# Order.net
KiCad netlist of a schematic drawn in EAGLE
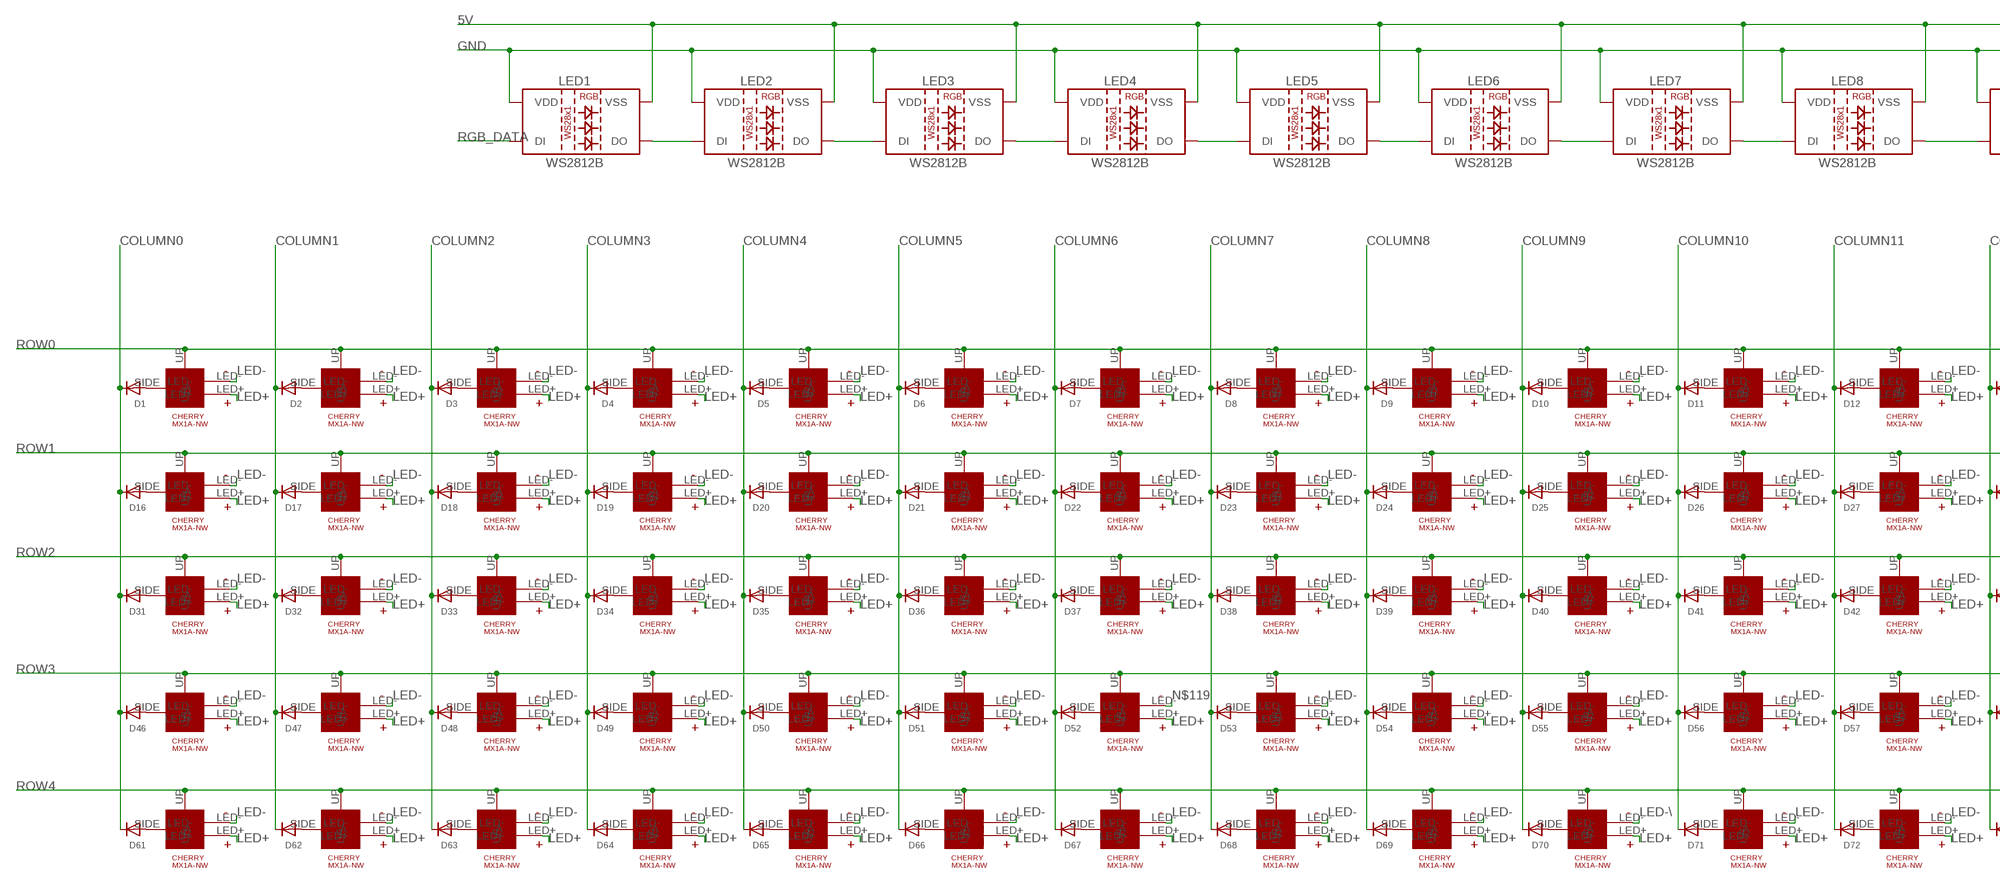
[diagram p0: schematic, sheet 1, part 1 of 2]
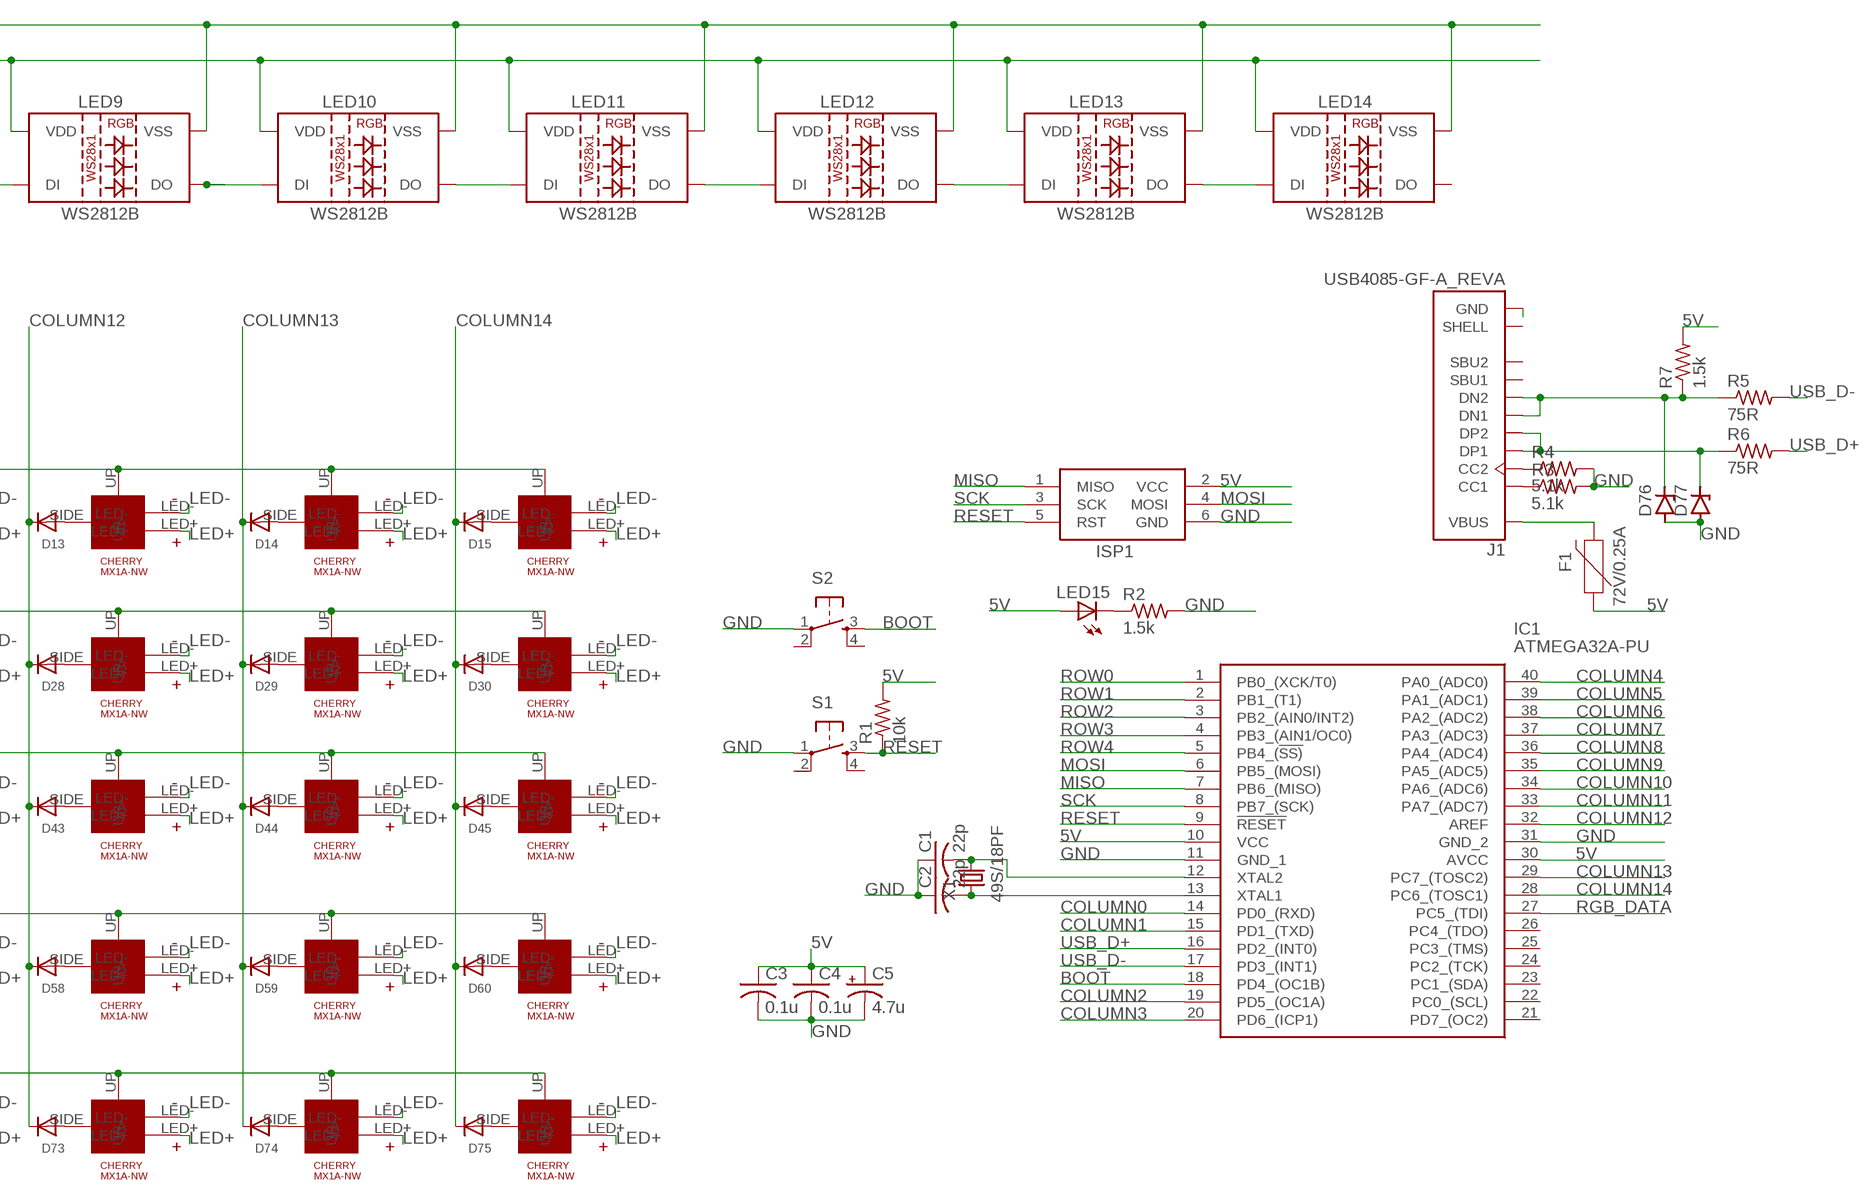
[diagram p1: schematic, sheet 1, part 2 of 2]

(export (version "E")
  (design (tool "Eeschema 10.0.6"))
  (components
    (comp (ref "C1")
      (value "22p")
      (footprint "eagle-import:C025-025X050")
      (libsource (lib "eagle-import") (part "C-US025-025X050"))
    )
    (comp (ref "C2")
      (value "22p")
      (footprint "eagle-import:C025-025X050")
      (libsource (lib "eagle-import") (part "C-US025-025X050"))
    )
    (comp (ref "C3")
      (value "0.1u")
      (footprint "eagle-import:C025-025X050")
      (libsource (lib "eagle-import") (part "C-US025-025X050"))
    )
    (comp (ref "C4")
      (value "0.1u")
      (footprint "eagle-import:C025-025X050")
      (libsource (lib "eagle-import") (part "C-US025-025X050"))
    )
    (comp (ref "C5")
      (value "4.7u")
      (footprint "eagle-import:E2-4")
      (libsource (lib "eagle-import") (part "CPOL-USE2-4"))
    )
    (comp (ref "D1")
      (value "DIODEDO-1N4148")
      (footprint "eagle-import:DO-1N4148")
      (libsource (lib "eagle-import") (part "DIODEDO-1N4148"))
    )
    (comp (ref "D2")
      (value "DIODEDO-1N4148")
      (footprint "eagle-import:DO-1N4148")
      (libsource (lib "eagle-import") (part "DIODEDO-1N4148"))
    )
    (comp (ref "D3")
      (value "DIODEDO-1N4148")
      (footprint "eagle-import:DO-1N4148")
      (libsource (lib "eagle-import") (part "DIODEDO-1N4148"))
    )
    (comp (ref "D4")
      (value "DIODEDO-1N4148")
      (footprint "eagle-import:DO-1N4148")
      (libsource (lib "eagle-import") (part "DIODEDO-1N4148"))
    )
    (comp (ref "D5")
      (value "DIODEDO-1N4148")
      (footprint "eagle-import:DO-1N4148")
      (libsource (lib "eagle-import") (part "DIODEDO-1N4148"))
    )
    (comp (ref "D6")
      (value "DIODEDO-1N4148")
      (footprint "eagle-import:DO-1N4148")
      (libsource (lib "eagle-import") (part "DIODEDO-1N4148"))
    )
    (comp (ref "D7")
      (value "DIODEDO-1N4148")
      (footprint "eagle-import:DO-1N4148")
      (libsource (lib "eagle-import") (part "DIODEDO-1N4148"))
    )
    (comp (ref "D8")
      (value "DIODEDO-1N4148")
      (footprint "eagle-import:DO-1N4148")
      (libsource (lib "eagle-import") (part "DIODEDO-1N4148"))
    )
    (comp (ref "D9")
      (value "DIODEDO-1N4148")
      (footprint "eagle-import:DO-1N4148")
      (libsource (lib "eagle-import") (part "DIODEDO-1N4148"))
    )
    (comp (ref "D10")
      (value "DIODEDO-1N4148")
      (footprint "eagle-import:DO-1N4148")
      (libsource (lib "eagle-import") (part "DIODEDO-1N4148"))
    )
    (comp (ref "D11")
      (value "DIODEDO-1N4148")
      (footprint "eagle-import:DO-1N4148")
      (libsource (lib "eagle-import") (part "DIODEDO-1N4148"))
    )
    (comp (ref "D12")
      (value "DIODEDO-1N4148")
      (footprint "eagle-import:DO-1N4148")
      (libsource (lib "eagle-import") (part "DIODEDO-1N4148"))
    )
    (comp (ref "D13")
      (value "DIODEDO-1N4148")
      (footprint "eagle-import:DO-1N4148")
      (libsource (lib "eagle-import") (part "DIODEDO-1N4148"))
    )
    (comp (ref "D14")
      (value "DIODEDO-1N4148")
      (footprint "eagle-import:DO-1N4148")
      (libsource (lib "eagle-import") (part "DIODEDO-1N4148"))
    )
    (comp (ref "D15")
      (value "DIODEDO-1N4148")
      (footprint "eagle-import:DO-1N4148")
      (libsource (lib "eagle-import") (part "DIODEDO-1N4148"))
    )
    (comp (ref "D16")
      (value "DIODEDO-1N4148")
      (footprint "eagle-import:DO-1N4148")
      (libsource (lib "eagle-import") (part "DIODEDO-1N4148"))
    )
    (comp (ref "D17")
      (value "DIODEDO-1N4148")
      (footprint "eagle-import:DO-1N4148")
      (libsource (lib "eagle-import") (part "DIODEDO-1N4148"))
    )
    (comp (ref "D18")
      (value "DIODEDO-1N4148")
      (footprint "eagle-import:DO-1N4148")
      (libsource (lib "eagle-import") (part "DIODEDO-1N4148"))
    )
    (comp (ref "D19")
      (value "DIODEDO-1N4148")
      (footprint "eagle-import:DO-1N4148")
      (libsource (lib "eagle-import") (part "DIODEDO-1N4148"))
    )
    (comp (ref "D20")
      (value "DIODEDO-1N4148")
      (footprint "eagle-import:DO-1N4148")
      (libsource (lib "eagle-import") (part "DIODEDO-1N4148"))
    )
    (comp (ref "D21")
      (value "DIODEDO-1N4148")
      (footprint "eagle-import:DO-1N4148")
      (libsource (lib "eagle-import") (part "DIODEDO-1N4148"))
    )
    (comp (ref "D22")
      (value "DIODEDO-1N4148")
      (footprint "eagle-import:DO-1N4148")
      (libsource (lib "eagle-import") (part "DIODEDO-1N4148"))
    )
    (comp (ref "D23")
      (value "DIODEDO-1N4148")
      (footprint "eagle-import:DO-1N4148")
      (libsource (lib "eagle-import") (part "DIODEDO-1N4148"))
    )
    (comp (ref "D24")
      (value "DIODEDO-1N4148")
      (footprint "eagle-import:DO-1N4148")
      (libsource (lib "eagle-import") (part "DIODEDO-1N4148"))
    )
    (comp (ref "D25")
      (value "DIODEDO-1N4148")
      (footprint "eagle-import:DO-1N4148")
      (libsource (lib "eagle-import") (part "DIODEDO-1N4148"))
    )
    (comp (ref "D26")
      (value "DIODEDO-1N4148")
      (footprint "eagle-import:DO-1N4148")
      (libsource (lib "eagle-import") (part "DIODEDO-1N4148"))
    )
    (comp (ref "D27")
      (value "DIODEDO-1N4148")
      (footprint "eagle-import:DO-1N4148")
      (libsource (lib "eagle-import") (part "DIODEDO-1N4148"))
    )
    (comp (ref "D28")
      (value "DIODEDO-1N4148")
      (footprint "eagle-import:DO-1N4148")
      (libsource (lib "eagle-import") (part "DIODEDO-1N4148"))
    )
    (comp (ref "D29")
      (value "DIODEDO-1N4148")
      (footprint "eagle-import:DO-1N4148")
      (libsource (lib "eagle-import") (part "DIODEDO-1N4148"))
    )
    (comp (ref "D30")
      (value "DIODEDO-1N4148")
      (footprint "eagle-import:DO-1N4148")
      (libsource (lib "eagle-import") (part "DIODEDO-1N4148"))
    )
    (comp (ref "D31")
      (value "DIODEDO-1N4148")
      (footprint "eagle-import:DO-1N4148")
      (libsource (lib "eagle-import") (part "DIODEDO-1N4148"))
    )
    (comp (ref "D32")
      (value "DIODEDO-1N4148")
      (footprint "eagle-import:DO-1N4148")
      (libsource (lib "eagle-import") (part "DIODEDO-1N4148"))
    )
    (comp (ref "D33")
      (value "DIODEDO-1N4148")
      (footprint "eagle-import:DO-1N4148")
      (libsource (lib "eagle-import") (part "DIODEDO-1N4148"))
    )
    (comp (ref "D34")
      (value "DIODEDO-1N4148")
      (footprint "eagle-import:DO-1N4148")
      (libsource (lib "eagle-import") (part "DIODEDO-1N4148"))
    )
    (comp (ref "D35")
      (value "DIODEDO-1N4148")
      (footprint "eagle-import:DO-1N4148")
      (libsource (lib "eagle-import") (part "DIODEDO-1N4148"))
    )
    (comp (ref "D36")
      (value "DIODEDO-1N4148")
      (footprint "eagle-import:DO-1N4148")
      (libsource (lib "eagle-import") (part "DIODEDO-1N4148"))
    )
    (comp (ref "D37")
      (value "DIODEDO-1N4148")
      (footprint "eagle-import:DO-1N4148")
      (libsource (lib "eagle-import") (part "DIODEDO-1N4148"))
    )
    (comp (ref "D38")
      (value "DIODEDO-1N4148")
      (footprint "eagle-import:DO-1N4148")
      (libsource (lib "eagle-import") (part "DIODEDO-1N4148"))
    )
    (comp (ref "D39")
      (value "DIODEDO-1N4148")
      (footprint "eagle-import:DO-1N4148")
      (libsource (lib "eagle-import") (part "DIODEDO-1N4148"))
    )
    (comp (ref "D40")
      (value "DIODEDO-1N4148")
      (footprint "eagle-import:DO-1N4148")
      (libsource (lib "eagle-import") (part "DIODEDO-1N4148"))
    )
    (comp (ref "D41")
      (value "DIODEDO-1N4148")
      (footprint "eagle-import:DO-1N4148")
      (libsource (lib "eagle-import") (part "DIODEDO-1N4148"))
    )
    (comp (ref "D42")
      (value "DIODEDO-1N4148")
      (footprint "eagle-import:DO-1N4148")
      (libsource (lib "eagle-import") (part "DIODEDO-1N4148"))
    )
    (comp (ref "D43")
      (value "DIODEDO-1N4148")
      (footprint "eagle-import:DO-1N4148")
      (libsource (lib "eagle-import") (part "DIODEDO-1N4148"))
    )
    (comp (ref "D44")
      (value "DIODEDO-1N4148")
      (footprint "eagle-import:DO-1N4148")
      (libsource (lib "eagle-import") (part "DIODEDO-1N4148"))
    )
    (comp (ref "D45")
      (value "DIODEDO-1N4148")
      (footprint "eagle-import:DO-1N4148")
      (libsource (lib "eagle-import") (part "DIODEDO-1N4148"))
    )
    (comp (ref "D46")
      (value "DIODEDO-1N4148")
      (footprint "eagle-import:DO-1N4148")
      (libsource (lib "eagle-import") (part "DIODEDO-1N4148"))
    )
    (comp (ref "D47")
      (value "DIODEDO-1N4148")
      (footprint "eagle-import:DO-1N4148")
      (libsource (lib "eagle-import") (part "DIODEDO-1N4148"))
    )
    (comp (ref "D48")
      (value "DIODEDO-1N4148")
      (footprint "eagle-import:DO-1N4148")
      (libsource (lib "eagle-import") (part "DIODEDO-1N4148"))
    )
    (comp (ref "D49")
      (value "DIODEDO-1N4148")
      (footprint "eagle-import:DO-1N4148")
      (libsource (lib "eagle-import") (part "DIODEDO-1N4148"))
    )
    (comp (ref "D50")
      (value "DIODEDO-1N4148")
      (footprint "eagle-import:DO-1N4148")
      (libsource (lib "eagle-import") (part "DIODEDO-1N4148"))
    )
    (comp (ref "D51")
      (value "DIODEDO-1N4148")
      (footprint "eagle-import:DO-1N4148")
      (libsource (lib "eagle-import") (part "DIODEDO-1N4148"))
    )
    (comp (ref "D52")
      (value "DIODEDO-1N4148")
      (footprint "eagle-import:DO-1N4148")
      (libsource (lib "eagle-import") (part "DIODEDO-1N4148"))
    )
    (comp (ref "D53")
      (value "DIODEDO-1N4148")
      (footprint "eagle-import:DO-1N4148")
      (libsource (lib "eagle-import") (part "DIODEDO-1N4148"))
    )
    (comp (ref "D54")
      (value "DIODEDO-1N4148")
      (footprint "eagle-import:DO-1N4148")
      (libsource (lib "eagle-import") (part "DIODEDO-1N4148"))
    )
    (comp (ref "D55")
      (value "DIODEDO-1N4148")
      (footprint "eagle-import:DO-1N4148")
      (libsource (lib "eagle-import") (part "DIODEDO-1N4148"))
    )
    (comp (ref "D56")
      (value "DIODEDO-1N4148")
      (footprint "eagle-import:DO-1N4148")
      (libsource (lib "eagle-import") (part "DIODEDO-1N4148"))
    )
    (comp (ref "D57")
      (value "DIODEDO-1N4148")
      (footprint "eagle-import:DO-1N4148")
      (libsource (lib "eagle-import") (part "DIODEDO-1N4148"))
    )
    (comp (ref "D58")
      (value "DIODEDO-1N4148")
      (footprint "eagle-import:DO-1N4148")
      (libsource (lib "eagle-import") (part "DIODEDO-1N4148"))
    )
    (comp (ref "D59")
      (value "DIODEDO-1N4148")
      (footprint "eagle-import:DO-1N4148")
      (libsource (lib "eagle-import") (part "DIODEDO-1N4148"))
    )
    (comp (ref "D60")
      (value "DIODEDO-1N4148")
      (footprint "eagle-import:DO-1N4148")
      (libsource (lib "eagle-import") (part "DIODEDO-1N4148"))
    )
    (comp (ref "D61")
      (value "DIODEDO-1N4148")
      (footprint "eagle-import:DO-1N4148")
      (libsource (lib "eagle-import") (part "DIODEDO-1N4148"))
    )
    (comp (ref "D62")
      (value "DIODEDO-1N4148")
      (footprint "eagle-import:DO-1N4148")
      (libsource (lib "eagle-import") (part "DIODEDO-1N4148"))
    )
    (comp (ref "D63")
      (value "DIODEDO-1N4148")
      (footprint "eagle-import:DO-1N4148")
      (libsource (lib "eagle-import") (part "DIODEDO-1N4148"))
    )
    (comp (ref "D64")
      (value "DIODEDO-1N4148")
      (footprint "eagle-import:DO-1N4148")
      (libsource (lib "eagle-import") (part "DIODEDO-1N4148"))
    )
    (comp (ref "D65")
      (value "DIODEDO-1N4148")
      (footprint "eagle-import:DO-1N4148")
      (libsource (lib "eagle-import") (part "DIODEDO-1N4148"))
    )
    (comp (ref "D66")
      (value "DIODEDO-1N4148")
      (footprint "eagle-import:DO-1N4148")
      (libsource (lib "eagle-import") (part "DIODEDO-1N4148"))
    )
    (comp (ref "D67")
      (value "DIODEDO-1N4148")
      (footprint "eagle-import:DO-1N4148")
      (libsource (lib "eagle-import") (part "DIODEDO-1N4148"))
    )
    (comp (ref "D68")
      (value "DIODEDO-1N4148")
      (footprint "eagle-import:DO-1N4148")
      (libsource (lib "eagle-import") (part "DIODEDO-1N4148"))
    )
    (comp (ref "D69")
      (value "DIODEDO-1N4148")
      (footprint "eagle-import:DO-1N4148")
      (libsource (lib "eagle-import") (part "DIODEDO-1N4148"))
    )
    (comp (ref "D70")
      (value "DIODEDO-1N4148")
      (footprint "eagle-import:DO-1N4148")
      (libsource (lib "eagle-import") (part "DIODEDO-1N4148"))
    )
    (comp (ref "D71")
      (value "DIODEDO-1N4148")
      (footprint "eagle-import:DO-1N4148")
      (libsource (lib "eagle-import") (part "DIODEDO-1N4148"))
    )
    (comp (ref "D72")
      (value "DIODEDO-1N4148")
      (footprint "eagle-import:DO-1N4148")
      (libsource (lib "eagle-import") (part "DIODEDO-1N4148"))
    )
    (comp (ref "D73")
      (value "DIODEDO-1N4148")
      (footprint "eagle-import:DO-1N4148")
      (libsource (lib "eagle-import") (part "DIODEDO-1N4148"))
    )
    (comp (ref "D74")
      (value "DIODEDO-1N4148")
      (footprint "eagle-import:DO-1N4148")
      (libsource (lib "eagle-import") (part "DIODEDO-1N4148"))
    )
    (comp (ref "D75")
      (value "DIODEDO-1N4148")
      (footprint "eagle-import:DO-1N4148")
      (libsource (lib "eagle-import") (part "DIODEDO-1N4148"))
    )
    (comp (ref "D76")
      (value "ZENER-DIODEDO34-7")
      (footprint "eagle-import:DO34Z7")
      (libsource (lib "eagle-import") (part "ZENER-DIODEDO34-7"))
    )
    (comp (ref "D77")
      (value "ZENER-DIODEDO34-7")
      (footprint "eagle-import:DO34Z7")
      (libsource (lib "eagle-import") (part "ZENER-DIODEDO34-7"))
    )
    (comp (ref "F1")
      (value "72V/0.25A")
      (footprint "eagle-import:PTH")
      (libsource (lib "eagle-import") (part "PPTC_PTH"))
    )
    (comp (ref "IC1")
      (value "ATMEGA32A-PU")
      (footprint "eagle-import:DIP1556W56P254L5232H483Q40N")
      (fields (field (name "MOUSER_PART_NUMBER") "556-ATMEGA32A-PU"))
      (libsource (lib "eagle-import") (part "ATMEGA32A-PU"))
    )
    (comp (ref "ISP1")
      (value "AVRISP-6")
      (footprint "eagle-import:AVRISP")
      (libsource (lib "eagle-import") (part "AVRISP-6"))
    )
    (comp (ref "J1")
      (value "USB4085-GF-A_REVA")
      (footprint "eagle-import:GCT_USB4085-GF-A_REVA")
      (fields
        (field (name "DIGI-KEY_PART_NUMBER") "2073-USB4085-GF-ACT-ND")
        (field (name "MF") "Global Connector Technology")
        (field (name "MP") "USB4085-GF-A")
      )
      (libsource (lib "eagle-import") (part "USB4085-GF-A_REVA"))
    )
    (comp (ref "LED1")
      (value "WS2812B")
      (footprint "eagle-import:WS2812B")
      (libsource (lib "eagle-import") (part "WS2812B"))
    )
    (comp (ref "LED2")
      (value "WS2812B")
      (footprint "eagle-import:WS2812B")
      (libsource (lib "eagle-import") (part "WS2812B"))
    )
    (comp (ref "LED3")
      (value "WS2812B")
      (footprint "eagle-import:WS2812B")
      (libsource (lib "eagle-import") (part "WS2812B"))
    )
    (comp (ref "LED4")
      (value "WS2812B")
      (footprint "eagle-import:WS2812B")
      (libsource (lib "eagle-import") (part "WS2812B"))
    )
    (comp (ref "LED5")
      (value "WS2812B")
      (footprint "eagle-import:WS2812B")
      (libsource (lib "eagle-import") (part "WS2812B"))
    )
    (comp (ref "LED6")
      (value "WS2812B")
      (footprint "eagle-import:WS2812B")
      (libsource (lib "eagle-import") (part "WS2812B"))
    )
    (comp (ref "LED7")
      (value "WS2812B")
      (footprint "eagle-import:WS2812B")
      (libsource (lib "eagle-import") (part "WS2812B"))
    )
    (comp (ref "LED8")
      (value "WS2812B")
      (footprint "eagle-import:WS2812B")
      (libsource (lib "eagle-import") (part "WS2812B"))
    )
    (comp (ref "LED9")
      (value "WS2812B")
      (footprint "eagle-import:WS2812B")
      (libsource (lib "eagle-import") (part "WS2812B"))
    )
    (comp (ref "LED10")
      (value "WS2812B")
      (footprint "eagle-import:WS2812B")
      (libsource (lib "eagle-import") (part "WS2812B"))
    )
    (comp (ref "LED11")
      (value "WS2812B")
      (footprint "eagle-import:WS2812B")
      (libsource (lib "eagle-import") (part "WS2812B"))
    )
    (comp (ref "LED12")
      (value "WS2812B")
      (footprint "eagle-import:WS2812B")
      (libsource (lib "eagle-import") (part "WS2812B"))
    )
    (comp (ref "LED13")
      (value "WS2812B")
      (footprint "eagle-import:WS2812B")
      (libsource (lib "eagle-import") (part "WS2812B"))
    )
    (comp (ref "LED14")
      (value "WS2812B")
      (footprint "eagle-import:WS2812B")
      (libsource (lib "eagle-import") (part "WS2812B"))
    )
    (comp (ref "LED15")
      (value "LED3MM")
      (footprint "eagle-import:LED3MM")
      (libsource (lib "eagle-import") (part "LED3MM"))
    )
    (comp (ref "R1")
      (value "10k")
      (footprint "eagle-import:0207_9")
      (libsource (lib "eagle-import") (part "R-US_0207/9"))
    )
    (comp (ref "R2")
      (value "1.5k")
      (footprint "eagle-import:0207_9")
      (libsource (lib "eagle-import") (part "R-US_0207/9"))
    )
    (comp (ref "R3")
      (value "5.1k")
      (footprint "eagle-import:0207_9")
      (libsource (lib "eagle-import") (part "R-US_0207/9"))
    )
    (comp (ref "R4")
      (value "5.1k")
      (footprint "eagle-import:0207_9")
      (libsource (lib "eagle-import") (part "R-US_0207/9"))
    )
    (comp (ref "R5")
      (value "75R")
      (footprint "eagle-import:0207_9")
      (libsource (lib "eagle-import") (part "R-US_0207/9"))
    )
    (comp (ref "R6")
      (value "75R")
      (footprint "eagle-import:0207_9")
      (libsource (lib "eagle-import") (part "R-US_0207/9"))
    )
    (comp (ref "R7")
      (value "1.5k")
      (footprint "eagle-import:0207_9")
      (libsource (lib "eagle-import") (part "R-US_0207/9"))
    )
    (comp (ref "S1")
      (value "TAC_SWITCHPTH")
      (footprint "eagle-import:TACTILE-PTH")
      (libsource (lib "eagle-import") (part "TAC_SWITCHPTH"))
    )
    (comp (ref "S2")
      (value "TAC_SWITCHPTH")
      (footprint "eagle-import:TACTILE-PTH")
      (libsource (lib "eagle-import") (part "TAC_SWITCHPTH"))
    )
    (comp (ref "U$1")
      (value "CHERRY-MX1A-E1NW-LED")
      (footprint "eagle-import:CHERRYMX-NN-LED")
      (libsource (lib "eagle-import") (part "CHERRY-MX1A-E1NW-LED"))
    )
    (comp (ref "U$2")
      (value "CHERRY-MX1A-E1NW-LED")
      (footprint "eagle-import:CHERRYMX-NN-LED")
      (libsource (lib "eagle-import") (part "CHERRY-MX1A-E1NW-LED"))
    )
    (comp (ref "U$3")
      (value "CHERRY-MX1A-E1NW-LED")
      (footprint "eagle-import:CHERRYMX-NN-LED")
      (libsource (lib "eagle-import") (part "CHERRY-MX1A-E1NW-LED"))
    )
    (comp (ref "U$4")
      (value "CHERRY-MX1A-E1NW-LED")
      (footprint "eagle-import:CHERRYMX-NN-LED")
      (libsource (lib "eagle-import") (part "CHERRY-MX1A-E1NW-LED"))
    )
    (comp (ref "U$5")
      (value "CHERRY-MX1A-E1NW-LED")
      (footprint "eagle-import:CHERRYMX-NN-LED")
      (libsource (lib "eagle-import") (part "CHERRY-MX1A-E1NW-LED"))
    )
    (comp (ref "U$6")
      (value "CHERRY-MX1A-E1NW-LED")
      (footprint "eagle-import:CHERRYMX-NN-LED")
      (libsource (lib "eagle-import") (part "CHERRY-MX1A-E1NW-LED"))
    )
    (comp (ref "U$7")
      (value "CHERRY-MX1A-E1NW-LED")
      (footprint "eagle-import:CHERRYMX-NN-LED")
      (libsource (lib "eagle-import") (part "CHERRY-MX1A-E1NW-LED"))
    )
    (comp (ref "U$8")
      (value "CHERRY-MX1A-E1NW-LED")
      (footprint "eagle-import:CHERRYMX-NN-LED")
      (libsource (lib "eagle-import") (part "CHERRY-MX1A-E1NW-LED"))
    )
    (comp (ref "U$9")
      (value "CHERRY-MX1A-E1NW-LED")
      (footprint "eagle-import:CHERRYMX-NN-LED")
      (libsource (lib "eagle-import") (part "CHERRY-MX1A-E1NW-LED"))
    )
    (comp (ref "U$10")
      (value "CHERRY-MX1A-E1NW-LED")
      (footprint "eagle-import:CHERRYMX-NN-LED")
      (libsource (lib "eagle-import") (part "CHERRY-MX1A-E1NW-LED"))
    )
    (comp (ref "U$11")
      (value "CHERRY-MX1A-E1NW-LED")
      (footprint "eagle-import:CHERRYMX-NN-LED")
      (libsource (lib "eagle-import") (part "CHERRY-MX1A-E1NW-LED"))
    )
    (comp (ref "U$12")
      (value "CHERRY-MX1A-E1NW-LED")
      (footprint "eagle-import:CHERRYMX-NN-LED")
      (libsource (lib "eagle-import") (part "CHERRY-MX1A-E1NW-LED"))
    )
    (comp (ref "U$13")
      (value "CHERRY-MX1A-E1NW-LED")
      (footprint "eagle-import:CHERRYMX-NN-LED")
      (libsource (lib "eagle-import") (part "CHERRY-MX1A-E1NW-LED"))
    )
    (comp (ref "U$14")
      (value "CHERRY-MX1A-E1NW-LED")
      (footprint "eagle-import:CHERRYMX-NN-LED")
      (libsource (lib "eagle-import") (part "CHERRY-MX1A-E1NW-LED"))
    )
    (comp (ref "U$15")
      (value "CHERRY-MX1A-E1NW-LED")
      (footprint "eagle-import:CHERRYMX-NN-LED")
      (libsource (lib "eagle-import") (part "CHERRY-MX1A-E1NW-LED"))
    )
    (comp (ref "U$16")
      (value "CHERRY-MX1A-E1NW-LED")
      (footprint "eagle-import:CHERRYMX-NN-LED")
      (libsource (lib "eagle-import") (part "CHERRY-MX1A-E1NW-LED"))
    )
    (comp (ref "U$17")
      (value "CHERRY-MX1A-E1NW-LED")
      (footprint "eagle-import:CHERRYMX-NN-LED")
      (libsource (lib "eagle-import") (part "CHERRY-MX1A-E1NW-LED"))
    )
    (comp (ref "U$18")
      (value "CHERRY-MX1A-E1NW-LED")
      (footprint "eagle-import:CHERRYMX-NN-LED")
      (libsource (lib "eagle-import") (part "CHERRY-MX1A-E1NW-LED"))
    )
    (comp (ref "U$19")
      (value "CHERRY-MX1A-E1NW-LED")
      (footprint "eagle-import:CHERRYMX-NN-LED")
      (libsource (lib "eagle-import") (part "CHERRY-MX1A-E1NW-LED"))
    )
    (comp (ref "U$20")
      (value "CHERRY-MX1A-E1NW-LED")
      (footprint "eagle-import:CHERRYMX-NN-LED")
      (libsource (lib "eagle-import") (part "CHERRY-MX1A-E1NW-LED"))
    )
    (comp (ref "U$21")
      (value "CHERRY-MX1A-E1NW-LED")
      (footprint "eagle-import:CHERRYMX-NN-LED")
      (libsource (lib "eagle-import") (part "CHERRY-MX1A-E1NW-LED"))
    )
    (comp (ref "U$22")
      (value "CHERRY-MX1A-E1NW-LED")
      (footprint "eagle-import:CHERRYMX-NN-LED")
      (libsource (lib "eagle-import") (part "CHERRY-MX1A-E1NW-LED"))
    )
    (comp (ref "U$23")
      (value "CHERRY-MX1A-E1NW-LED")
      (footprint "eagle-import:CHERRYMX-NN-LED")
      (libsource (lib "eagle-import") (part "CHERRY-MX1A-E1NW-LED"))
    )
    (comp (ref "U$24")
      (value "CHERRY-MX1A-E1NW-LED")
      (footprint "eagle-import:CHERRYMX-NN-LED")
      (libsource (lib "eagle-import") (part "CHERRY-MX1A-E1NW-LED"))
    )
    (comp (ref "U$25")
      (value "CHERRY-MX1A-E1NW-LED")
      (footprint "eagle-import:CHERRYMX-NN-LED")
      (libsource (lib "eagle-import") (part "CHERRY-MX1A-E1NW-LED"))
    )
    (comp (ref "U$26")
      (value "CHERRY-MX1A-E1NW-LED")
      (footprint "eagle-import:CHERRYMX-NN-LED")
      (libsource (lib "eagle-import") (part "CHERRY-MX1A-E1NW-LED"))
    )
    (comp (ref "U$27")
      (value "CHERRY-MX1A-E1NW-LED")
      (footprint "eagle-import:CHERRYMX-NN-LED")
      (libsource (lib "eagle-import") (part "CHERRY-MX1A-E1NW-LED"))
    )
    (comp (ref "U$28")
      (value "CHERRY-MX1A-E1NW-LED")
      (footprint "eagle-import:CHERRYMX-NN-LED")
      (libsource (lib "eagle-import") (part "CHERRY-MX1A-E1NW-LED"))
    )
    (comp (ref "U$29")
      (value "CHERRY-MX1A-E1NW-LED")
      (footprint "eagle-import:CHERRYMX-NN-LED")
      (libsource (lib "eagle-import") (part "CHERRY-MX1A-E1NW-LED"))
    )
    (comp (ref "U$30")
      (value "CHERRY-MX1A-E1NW-LED")
      (footprint "eagle-import:CHERRYMX-NN-LED")
      (libsource (lib "eagle-import") (part "CHERRY-MX1A-E1NW-LED"))
    )
    (comp (ref "U$31")
      (value "CHERRY-MX1A-E1NW-LED")
      (footprint "eagle-import:CHERRYMX-NN-LED")
      (libsource (lib "eagle-import") (part "CHERRY-MX1A-E1NW-LED"))
    )
    (comp (ref "U$32")
      (value "CHERRY-MX1A-E1NW-LED")
      (footprint "eagle-import:CHERRYMX-NN-LED")
      (libsource (lib "eagle-import") (part "CHERRY-MX1A-E1NW-LED"))
    )
    (comp (ref "U$33")
      (value "CHERRY-MX1A-E1NW-LED")
      (footprint "eagle-import:CHERRYMX-NN-LED")
      (libsource (lib "eagle-import") (part "CHERRY-MX1A-E1NW-LED"))
    )
    (comp (ref "U$34")
      (value "CHERRY-MX1A-E1NW-LED")
      (footprint "eagle-import:CHERRYMX-NN-LED")
      (libsource (lib "eagle-import") (part "CHERRY-MX1A-E1NW-LED"))
    )
    (comp (ref "U$35")
      (value "CHERRY-MX1A-E1NW-LED")
      (footprint "eagle-import:CHERRYMX-NN-LED")
      (libsource (lib "eagle-import") (part "CHERRY-MX1A-E1NW-LED"))
    )
    (comp (ref "U$36")
      (value "CHERRY-MX1A-E1NW-LED")
      (footprint "eagle-import:CHERRYMX-NN-LED")
      (libsource (lib "eagle-import") (part "CHERRY-MX1A-E1NW-LED"))
    )
    (comp (ref "U$37")
      (value "CHERRY-MX1A-E1NW-LED")
      (footprint "eagle-import:CHERRYMX-NN-LED")
      (libsource (lib "eagle-import") (part "CHERRY-MX1A-E1NW-LED"))
    )
    (comp (ref "U$38")
      (value "CHERRY-MX1A-E1NW-LED")
      (footprint "eagle-import:CHERRYMX-NN-LED")
      (libsource (lib "eagle-import") (part "CHERRY-MX1A-E1NW-LED"))
    )
    (comp (ref "U$39")
      (value "CHERRY-MX1A-E1NW-LED")
      (footprint "eagle-import:CHERRYMX-NN-LED")
      (libsource (lib "eagle-import") (part "CHERRY-MX1A-E1NW-LED"))
    )
    (comp (ref "U$40")
      (value "CHERRY-MX1A-E1NW-LED")
      (footprint "eagle-import:CHERRYMX-NN-LED")
      (libsource (lib "eagle-import") (part "CHERRY-MX1A-E1NW-LED"))
    )
    (comp (ref "U$41")
      (value "CHERRY-MX1A-E1NW-LED")
      (footprint "eagle-import:CHERRYMX-NN-LED")
      (libsource (lib "eagle-import") (part "CHERRY-MX1A-E1NW-LED"))
    )
    (comp (ref "U$42")
      (value "CHERRY-MX1A-E1NW-LED")
      (footprint "eagle-import:CHERRYMX-NN-LED")
      (libsource (lib "eagle-import") (part "CHERRY-MX1A-E1NW-LED"))
    )
    (comp (ref "U$43")
      (value "CHERRY-MX1A-E1NW-LED")
      (footprint "eagle-import:CHERRYMX-NN-LED")
      (libsource (lib "eagle-import") (part "CHERRY-MX1A-E1NW-LED"))
    )
    (comp (ref "U$44")
      (value "CHERRY-MX1A-E1NW-LED")
      (footprint "eagle-import:CHERRYMX-NN-LED")
      (libsource (lib "eagle-import") (part "CHERRY-MX1A-E1NW-LED"))
    )
    (comp (ref "U$45")
      (value "CHERRY-MX1A-E1NW-LED")
      (footprint "eagle-import:CHERRYMX-NN-LED")
      (libsource (lib "eagle-import") (part "CHERRY-MX1A-E1NW-LED"))
    )
    (comp (ref "U$46")
      (value "CHERRY-MX1A-E1NW-LED")
      (footprint "eagle-import:CHERRYMX-NN-LED")
      (libsource (lib "eagle-import") (part "CHERRY-MX1A-E1NW-LED"))
    )
    (comp (ref "U$47")
      (value "CHERRY-MX1A-E1NW-LED")
      (footprint "eagle-import:CHERRYMX-NN-LED")
      (libsource (lib "eagle-import") (part "CHERRY-MX1A-E1NW-LED"))
    )
    (comp (ref "U$48")
      (value "CHERRY-MX1A-E1NW-LED")
      (footprint "eagle-import:CHERRYMX-NN-LED")
      (libsource (lib "eagle-import") (part "CHERRY-MX1A-E1NW-LED"))
    )
    (comp (ref "U$49")
      (value "CHERRY-MX1A-E1NW-LED")
      (footprint "eagle-import:CHERRYMX-NN-LED")
      (libsource (lib "eagle-import") (part "CHERRY-MX1A-E1NW-LED"))
    )
    (comp (ref "U$50")
      (value "CHERRY-MX1A-E1NW-LED")
      (footprint "eagle-import:CHERRYMX-NN-LED")
      (libsource (lib "eagle-import") (part "CHERRY-MX1A-E1NW-LED"))
    )
    (comp (ref "U$51")
      (value "CHERRY-MX1A-E1NW-LED")
      (footprint "eagle-import:CHERRYMX-NN-LED")
      (libsource (lib "eagle-import") (part "CHERRY-MX1A-E1NW-LED"))
    )
    (comp (ref "U$52")
      (value "CHERRY-MX1A-E1NW-LED")
      (footprint "eagle-import:CHERRYMX-NN-LED")
      (libsource (lib "eagle-import") (part "CHERRY-MX1A-E1NW-LED"))
    )
    (comp (ref "U$53")
      (value "CHERRY-MX1A-E1NW-LED")
      (footprint "eagle-import:CHERRYMX-NN-LED")
      (libsource (lib "eagle-import") (part "CHERRY-MX1A-E1NW-LED"))
    )
    (comp (ref "U$54")
      (value "CHERRY-MX1A-E1NW-LED")
      (footprint "eagle-import:CHERRYMX-NN-LED")
      (libsource (lib "eagle-import") (part "CHERRY-MX1A-E1NW-LED"))
    )
    (comp (ref "U$55")
      (value "CHERRY-MX1A-E1NW-LED")
      (footprint "eagle-import:CHERRYMX-NN-LED")
      (libsource (lib "eagle-import") (part "CHERRY-MX1A-E1NW-LED"))
    )
    (comp (ref "U$56")
      (value "CHERRY-MX1A-E1NW-LED")
      (footprint "eagle-import:CHERRYMX-NN-LED")
      (libsource (lib "eagle-import") (part "CHERRY-MX1A-E1NW-LED"))
    )
    (comp (ref "U$57")
      (value "CHERRY-MX1A-E1NW-LED")
      (footprint "eagle-import:CHERRYMX-NN-LED")
      (libsource (lib "eagle-import") (part "CHERRY-MX1A-E1NW-LED"))
    )
    (comp (ref "U$58")
      (value "CHERRY-MX1A-E1NW-LED")
      (footprint "eagle-import:CHERRYMX-NN-LED")
      (libsource (lib "eagle-import") (part "CHERRY-MX1A-E1NW-LED"))
    )
    (comp (ref "U$59")
      (value "CHERRY-MX1A-E1NW-LED")
      (footprint "eagle-import:CHERRYMX-NN-LED")
      (libsource (lib "eagle-import") (part "CHERRY-MX1A-E1NW-LED"))
    )
    (comp (ref "U$60")
      (value "CHERRY-MX1A-E1NW-LED")
      (footprint "eagle-import:CHERRYMX-NN-LED")
      (libsource (lib "eagle-import") (part "CHERRY-MX1A-E1NW-LED"))
    )
    (comp (ref "U$61")
      (value "CHERRY-MX1A-E1NW-LED")
      (footprint "eagle-import:CHERRYMX-NN-LED")
      (libsource (lib "eagle-import") (part "CHERRY-MX1A-E1NW-LED"))
    )
    (comp (ref "U$62")
      (value "CHERRY-MX1A-E1NW-LED")
      (footprint "eagle-import:CHERRYMX-NN-LED")
      (libsource (lib "eagle-import") (part "CHERRY-MX1A-E1NW-LED"))
    )
    (comp (ref "U$63")
      (value "CHERRY-MX1A-E1NW-LED")
      (footprint "eagle-import:CHERRYMX-NN-LED")
      (libsource (lib "eagle-import") (part "CHERRY-MX1A-E1NW-LED"))
    )
    (comp (ref "U$64")
      (value "CHERRY-MX1A-E1NW-LED")
      (footprint "eagle-import:CHERRYMX-NN-LED")
      (libsource (lib "eagle-import") (part "CHERRY-MX1A-E1NW-LED"))
    )
    (comp (ref "U$65")
      (value "CHERRY-MX1A-E1NW-LED")
      (footprint "eagle-import:CHERRYMX-NN-LED")
      (libsource (lib "eagle-import") (part "CHERRY-MX1A-E1NW-LED"))
    )
    (comp (ref "U$66")
      (value "CHERRY-MX1A-E1NW-LED")
      (footprint "eagle-import:CHERRYMX-NN-LED")
      (libsource (lib "eagle-import") (part "CHERRY-MX1A-E1NW-LED"))
    )
    (comp (ref "U$67")
      (value "CHERRY-MX1A-E1NW-LED")
      (footprint "eagle-import:CHERRYMX-NN-LED")
      (libsource (lib "eagle-import") (part "CHERRY-MX1A-E1NW-LED"))
    )
    (comp (ref "U$68")
      (value "CHERRY-MX1A-E1NW-LED")
      (footprint "eagle-import:CHERRYMX-NN-LED")
      (libsource (lib "eagle-import") (part "CHERRY-MX1A-E1NW-LED"))
    )
    (comp (ref "U$69")
      (value "CHERRY-MX1A-E1NW-LED")
      (footprint "eagle-import:CHERRYMX-NN-LED")
      (libsource (lib "eagle-import") (part "CHERRY-MX1A-E1NW-LED"))
    )
    (comp (ref "U$70")
      (value "CHERRY-MX1A-E1NW-LED")
      (footprint "eagle-import:CHERRYMX-NN-LED")
      (libsource (lib "eagle-import") (part "CHERRY-MX1A-E1NW-LED"))
    )
    (comp (ref "U$71")
      (value "CHERRY-MX1A-E1NW-LED")
      (footprint "eagle-import:CHERRYMX-NN-LED")
      (libsource (lib "eagle-import") (part "CHERRY-MX1A-E1NW-LED"))
    )
    (comp (ref "U$72")
      (value "CHERRY-MX1A-E1NW-LED")
      (footprint "eagle-import:CHERRYMX-NN-LED")
      (libsource (lib "eagle-import") (part "CHERRY-MX1A-E1NW-LED"))
    )
    (comp (ref "U$73")
      (value "CHERRY-MX1A-E1NW-LED")
      (footprint "eagle-import:CHERRYMX-NN-LED")
      (libsource (lib "eagle-import") (part "CHERRY-MX1A-E1NW-LED"))
    )
    (comp (ref "U$74")
      (value "CHERRY-MX1A-E1NW-LED")
      (footprint "eagle-import:CHERRYMX-NN-LED")
      (libsource (lib "eagle-import") (part "CHERRY-MX1A-E1NW-LED"))
    )
    (comp (ref "U$75")
      (value "CHERRY-MX1A-E1NW-LED")
      (footprint "eagle-import:CHERRYMX-NN-LED")
      (libsource (lib "eagle-import") (part "CHERRY-MX1A-E1NW-LED"))
    )
    (comp (ref "X1")
      (value "49S/18PF")
      (footprint "eagle-import:XTAL_HC49")
      (fields (field (name "MANUFACTURER") "Xinhunjing ") (field (name "CREATED_BY") "PCBLayout.com"))
      (libsource (lib "eagle-import") (part "49S/18PF"))
    )
  )
  (nets
    (net (code "1") (name "/5V") (class "Default")
      (node (ref "C3") (pin "1") (pinfunction "1_1") (pintype "passive"))
      (node (ref "C4") (pin "1") (pinfunction "1_1") (pintype "passive"))
      (node (ref "C5") (pin "+") (pinfunction "+_+") (pintype "passive"))
      (node (ref "F1") (pin "P$1") (pinfunction "1_P$1") (pintype "bidirectional"))
      (node (ref "IC1") (pin "10") (pinfunction "VCC_10") (pintype "bidirectional"))
      (node (ref "IC1") (pin "30") (pinfunction "AVCC_30") (pintype "bidirectional"))
      (node (ref "ISP1") (pin "2") (pinfunction "VCC_2") (pintype "power_in"))
      (node (ref "LED1") (pin "3") (pinfunction "VSS_3") (pintype "bidirectional"))
      (node (ref "LED10") (pin "3") (pinfunction "VSS_3") (pintype "bidirectional"))
      (node (ref "LED11") (pin "3") (pinfunction "VSS_3") (pintype "bidirectional"))
      (node (ref "LED12") (pin "3") (pinfunction "VSS_3") (pintype "bidirectional"))
      (node (ref "LED13") (pin "3") (pinfunction "VSS_3") (pintype "bidirectional"))
      (node (ref "LED14") (pin "3") (pinfunction "VSS_3") (pintype "bidirectional"))
      (node (ref "LED15") (pin "A") (pinfunction "A_A") (pintype "passive"))
      (node (ref "LED2") (pin "3") (pinfunction "VSS_3") (pintype "bidirectional"))
      (node (ref "LED3") (pin "3") (pinfunction "VSS_3") (pintype "bidirectional"))
      (node (ref "LED4") (pin "3") (pinfunction "VSS_3") (pintype "bidirectional"))
      (node (ref "LED5") (pin "3") (pinfunction "VSS_3") (pintype "bidirectional"))
      (node (ref "LED6") (pin "3") (pinfunction "VSS_3") (pintype "bidirectional"))
      (node (ref "LED7") (pin "3") (pinfunction "VSS_3") (pintype "bidirectional"))
      (node (ref "LED8") (pin "3") (pinfunction "VSS_3") (pintype "bidirectional"))
      (node (ref "LED9") (pin "3") (pinfunction "VSS_3") (pintype "bidirectional"))
      (node (ref "R1") (pin "2") (pinfunction "2_2") (pintype "passive"))
      (node (ref "R7") (pin "2") (pinfunction "2_2") (pintype "passive"))
    )
    (net (code "2") (name "/BOOT") (class "Default")
      (node (ref "IC1") (pin "18") (pinfunction "PD4_(OC1B)_18") (pintype "bidirectional"))
      (node (ref "S2") (pin "3") (pinfunction "3_3") (pintype "passive"))
    )
    (net (code "3") (name "/COLUMN0") (class "Default")
      (node (ref "D1") (pin "C") (pinfunction "C_C") (pintype "passive"))
      (node (ref "D16") (pin "C") (pinfunction "C_C") (pintype "passive"))
      (node (ref "D31") (pin "C") (pinfunction "C_C") (pintype "passive"))
      (node (ref "D46") (pin "C") (pinfunction "C_C") (pintype "passive"))
      (node (ref "D61") (pin "C") (pinfunction "C_C") (pintype "passive"))
      (node (ref "IC1") (pin "14") (pinfunction "PD0_(RXD)_14") (pintype "bidirectional"))
    )
    (net (code "4") (name "/COLUMN1") (class "Default")
      (node (ref "D17") (pin "C") (pinfunction "C_C") (pintype "passive"))
      (node (ref "D2") (pin "C") (pinfunction "C_C") (pintype "passive"))
      (node (ref "D32") (pin "C") (pinfunction "C_C") (pintype "passive"))
      (node (ref "D47") (pin "C") (pinfunction "C_C") (pintype "passive"))
      (node (ref "D62") (pin "C") (pinfunction "C_C") (pintype "passive"))
      (node (ref "IC1") (pin "15") (pinfunction "PD1_(TXD)_15") (pintype "bidirectional"))
    )
    (net (code "5") (name "/COLUMN2") (class "Default")
      (node (ref "D18") (pin "C") (pinfunction "C_C") (pintype "passive"))
      (node (ref "D3") (pin "C") (pinfunction "C_C") (pintype "passive"))
      (node (ref "D33") (pin "C") (pinfunction "C_C") (pintype "passive"))
      (node (ref "D48") (pin "C") (pinfunction "C_C") (pintype "passive"))
      (node (ref "D63") (pin "C") (pinfunction "C_C") (pintype "passive"))
      (node (ref "IC1") (pin "19") (pinfunction "PD5_(OC1A)_19") (pintype "bidirectional"))
    )
    (net (code "6") (name "/COLUMN3") (class "Default")
      (node (ref "D19") (pin "C") (pinfunction "C_C") (pintype "passive"))
      (node (ref "D34") (pin "C") (pinfunction "C_C") (pintype "passive"))
      (node (ref "D4") (pin "C") (pinfunction "C_C") (pintype "passive"))
      (node (ref "D49") (pin "C") (pinfunction "C_C") (pintype "passive"))
      (node (ref "D64") (pin "C") (pinfunction "C_C") (pintype "passive"))
      (node (ref "IC1") (pin "20") (pinfunction "PD6_(ICP1)_20") (pintype "bidirectional"))
    )
    (net (code "7") (name "/COLUMN4") (class "Default")
      (node (ref "D20") (pin "C") (pinfunction "C_C") (pintype "passive"))
      (node (ref "D35") (pin "C") (pinfunction "C_C") (pintype "passive"))
      (node (ref "D5") (pin "C") (pinfunction "C_C") (pintype "passive"))
      (node (ref "D50") (pin "C") (pinfunction "C_C") (pintype "passive"))
      (node (ref "D65") (pin "C") (pinfunction "C_C") (pintype "passive"))
      (node (ref "IC1") (pin "40") (pinfunction "PA0_(ADC0)_40") (pintype "bidirectional"))
    )
    (net (code "8") (name "/COLUMN5") (class "Default")
      (node (ref "D21") (pin "C") (pinfunction "C_C") (pintype "passive"))
      (node (ref "D36") (pin "C") (pinfunction "C_C") (pintype "passive"))
      (node (ref "D51") (pin "C") (pinfunction "C_C") (pintype "passive"))
      (node (ref "D6") (pin "C") (pinfunction "C_C") (pintype "passive"))
      (node (ref "D66") (pin "C") (pinfunction "C_C") (pintype "passive"))
      (node (ref "IC1") (pin "39") (pinfunction "PA1_(ADC1)_39") (pintype "bidirectional"))
    )
    (net (code "9") (name "/COLUMN6") (class "Default")
      (node (ref "D22") (pin "C") (pinfunction "C_C") (pintype "passive"))
      (node (ref "D37") (pin "C") (pinfunction "C_C") (pintype "passive"))
      (node (ref "D52") (pin "C") (pinfunction "C_C") (pintype "passive"))
      (node (ref "D67") (pin "C") (pinfunction "C_C") (pintype "passive"))
      (node (ref "D7") (pin "C") (pinfunction "C_C") (pintype "passive"))
      (node (ref "IC1") (pin "38") (pinfunction "PA2_(ADC2)_38") (pintype "bidirectional"))
    )
    (net (code "10") (name "/COLUMN7") (class "Default")
      (node (ref "D23") (pin "C") (pinfunction "C_C") (pintype "passive"))
      (node (ref "D38") (pin "C") (pinfunction "C_C") (pintype "passive"))
      (node (ref "D53") (pin "C") (pinfunction "C_C") (pintype "passive"))
      (node (ref "D68") (pin "C") (pinfunction "C_C") (pintype "passive"))
      (node (ref "D8") (pin "C") (pinfunction "C_C") (pintype "passive"))
      (node (ref "IC1") (pin "37") (pinfunction "PA3_(ADC3)_37") (pintype "bidirectional"))
    )
    (net (code "11") (name "/COLUMN8") (class "Default")
      (node (ref "D24") (pin "C") (pinfunction "C_C") (pintype "passive"))
      (node (ref "D39") (pin "C") (pinfunction "C_C") (pintype "passive"))
      (node (ref "D54") (pin "C") (pinfunction "C_C") (pintype "passive"))
      (node (ref "D69") (pin "C") (pinfunction "C_C") (pintype "passive"))
      (node (ref "D9") (pin "C") (pinfunction "C_C") (pintype "passive"))
      (node (ref "IC1") (pin "36") (pinfunction "PA4_(ADC4)_36") (pintype "bidirectional"))
    )
    (net (code "12") (name "/COLUMN9") (class "Default")
      (node (ref "D10") (pin "C") (pinfunction "C_C") (pintype "passive"))
      (node (ref "D25") (pin "C") (pinfunction "C_C") (pintype "passive"))
      (node (ref "D40") (pin "C") (pinfunction "C_C") (pintype "passive"))
      (node (ref "D55") (pin "C") (pinfunction "C_C") (pintype "passive"))
      (node (ref "D70") (pin "C") (pinfunction "C_C") (pintype "passive"))
      (node (ref "IC1") (pin "35") (pinfunction "PA5_(ADC5)_35") (pintype "bidirectional"))
    )
    (net (code "13") (name "/COLUMN10") (class "Default")
      (node (ref "D11") (pin "C") (pinfunction "C_C") (pintype "passive"))
      (node (ref "D26") (pin "C") (pinfunction "C_C") (pintype "passive"))
      (node (ref "D41") (pin "C") (pinfunction "C_C") (pintype "passive"))
      (node (ref "D56") (pin "C") (pinfunction "C_C") (pintype "passive"))
      (node (ref "D71") (pin "C") (pinfunction "C_C") (pintype "passive"))
      (node (ref "IC1") (pin "34") (pinfunction "PA6_(ADC6)_34") (pintype "bidirectional"))
    )
    (net (code "14") (name "/COLUMN11") (class "Default")
      (node (ref "D12") (pin "C") (pinfunction "C_C") (pintype "passive"))
      (node (ref "D27") (pin "C") (pinfunction "C_C") (pintype "passive"))
      (node (ref "D42") (pin "C") (pinfunction "C_C") (pintype "passive"))
      (node (ref "D57") (pin "C") (pinfunction "C_C") (pintype "passive"))
      (node (ref "D72") (pin "C") (pinfunction "C_C") (pintype "passive"))
      (node (ref "IC1") (pin "33") (pinfunction "PA7_(ADC7)_33") (pintype "bidirectional"))
    )
    (net (code "15") (name "/COLUMN12") (class "Default")
      (node (ref "D13") (pin "C") (pinfunction "C_C") (pintype "passive"))
      (node (ref "D28") (pin "C") (pinfunction "C_C") (pintype "passive"))
      (node (ref "D43") (pin "C") (pinfunction "C_C") (pintype "passive"))
      (node (ref "D58") (pin "C") (pinfunction "C_C") (pintype "passive"))
      (node (ref "D73") (pin "C") (pinfunction "C_C") (pintype "passive"))
      (node (ref "IC1") (pin "32") (pinfunction "AREF_32") (pintype "bidirectional"))
    )
    (net (code "16") (name "/COLUMN13") (class "Default")
      (node (ref "D14") (pin "C") (pinfunction "C_C") (pintype "passive"))
      (node (ref "D29") (pin "C") (pinfunction "C_C") (pintype "passive"))
      (node (ref "D44") (pin "C") (pinfunction "C_C") (pintype "passive"))
      (node (ref "D59") (pin "C") (pinfunction "C_C") (pintype "passive"))
      (node (ref "D74") (pin "C") (pinfunction "C_C") (pintype "passive"))
      (node (ref "IC1") (pin "29") (pinfunction "PC7_(TOSC2)_29") (pintype "bidirectional"))
    )
    (net (code "17") (name "/COLUMN14") (class "Default")
      (node (ref "D15") (pin "C") (pinfunction "C_C") (pintype "passive"))
      (node (ref "D30") (pin "C") (pinfunction "C_C") (pintype "passive"))
      (node (ref "D45") (pin "C") (pinfunction "C_C") (pintype "passive"))
      (node (ref "D60") (pin "C") (pinfunction "C_C") (pintype "passive"))
      (node (ref "D75") (pin "C") (pinfunction "C_C") (pintype "passive"))
      (node (ref "IC1") (pin "28") (pinfunction "PC6_(TOSC1)_28") (pintype "bidirectional"))
    )
    (net (code "18") (name "/GND") (class "Default")
      (node (ref "C1") (pin "1") (pinfunction "1_1") (pintype "passive"))
      (node (ref "C2") (pin "1") (pinfunction "1_1") (pintype "passive"))
      (node (ref "C3") (pin "2") (pinfunction "2_2") (pintype "passive"))
      (node (ref "C4") (pin "2") (pinfunction "2_2") (pintype "passive"))
      (node (ref "C5") (pin "-") (pinfunction "-_-") (pintype "passive"))
      (node (ref "D76") (pin "A") (pinfunction "A_A") (pintype "passive"))
      (node (ref "D77") (pin "A") (pinfunction "A_A") (pintype "passive"))
      (node (ref "IC1") (pin "11") (pinfunction "GND_1_11") (pintype "bidirectional"))
      (node (ref "IC1") (pin "31") (pinfunction "GND_2_31") (pintype "bidirectional"))
      (node (ref "ISP1") (pin "6") (pinfunction "GND_6") (pintype "power_in"))
      (node (ref "LED1") (pin "1") (pinfunction "VDD_1") (pintype "bidirectional"))
      (node (ref "LED10") (pin "1") (pinfunction "VDD_1") (pintype "bidirectional"))
      (node (ref "LED11") (pin "1") (pinfunction "VDD_1") (pintype "bidirectional"))
      (node (ref "LED12") (pin "1") (pinfunction "VDD_1") (pintype "bidirectional"))
      (node (ref "LED13") (pin "1") (pinfunction "VDD_1") (pintype "bidirectional"))
      (node (ref "LED14") (pin "1") (pinfunction "VDD_1") (pintype "bidirectional"))
      (node (ref "LED2") (pin "1") (pinfunction "VDD_1") (pintype "bidirectional"))
      (node (ref "LED3") (pin "1") (pinfunction "VDD_1") (pintype "bidirectional"))
      (node (ref "LED4") (pin "1") (pinfunction "VDD_1") (pintype "bidirectional"))
      (node (ref "LED5") (pin "1") (pinfunction "VDD_1") (pintype "bidirectional"))
      (node (ref "LED6") (pin "1") (pinfunction "VDD_1") (pintype "bidirectional"))
      (node (ref "LED7") (pin "1") (pinfunction "VDD_1") (pintype "bidirectional"))
      (node (ref "LED8") (pin "1") (pinfunction "VDD_1") (pintype "bidirectional"))
      (node (ref "LED9") (pin "1") (pinfunction "VDD_1") (pintype "bidirectional"))
      (node (ref "R2") (pin "2") (pinfunction "2_2") (pintype "passive"))
      (node (ref "R3") (pin "2") (pinfunction "2_2") (pintype "passive"))
      (node (ref "R4") (pin "2") (pinfunction "2_2") (pintype "passive"))
      (node (ref "S1") (pin "1") (pinfunction "1_1") (pintype "passive"))
      (node (ref "S2") (pin "1") (pinfunction "1_1") (pintype "passive"))
    )
    (net (code "19") (name "/LED+") (class "Default")
      (node (ref "U$1") (pin "LED+") (pinfunction "LED+_LED+") (pintype "bidirectional"))
      (node (ref "U$10") (pin "LED+") (pinfunction "LED+_LED+") (pintype "bidirectional"))
      (node (ref "U$11") (pin "LED+") (pinfunction "LED+_LED+") (pintype "bidirectional"))
      (node (ref "U$12") (pin "LED+") (pinfunction "LED+_LED+") (pintype "bidirectional"))
      (node (ref "U$13") (pin "LED+") (pinfunction "LED+_LED+") (pintype "bidirectional"))
      (node (ref "U$14") (pin "LED+") (pinfunction "LED+_LED+") (pintype "bidirectional"))
      (node (ref "U$15") (pin "LED+") (pinfunction "LED+_LED+") (pintype "bidirectional"))
      (node (ref "U$16") (pin "LED+") (pinfunction "LED+_LED+") (pintype "bidirectional"))
      (node (ref "U$17") (pin "LED+") (pinfunction "LED+_LED+") (pintype "bidirectional"))
      (node (ref "U$18") (pin "LED+") (pinfunction "LED+_LED+") (pintype "bidirectional"))
      (node (ref "U$19") (pin "LED+") (pinfunction "LED+_LED+") (pintype "bidirectional"))
      (node (ref "U$2") (pin "LED+") (pinfunction "LED+_LED+") (pintype "bidirectional"))
      (node (ref "U$20") (pin "LED+") (pinfunction "LED+_LED+") (pintype "bidirectional"))
      (node (ref "U$21") (pin "LED+") (pinfunction "LED+_LED+") (pintype "bidirectional"))
      (node (ref "U$22") (pin "LED+") (pinfunction "LED+_LED+") (pintype "bidirectional"))
      (node (ref "U$23") (pin "LED+") (pinfunction "LED+_LED+") (pintype "bidirectional"))
      (node (ref "U$24") (pin "LED+") (pinfunction "LED+_LED+") (pintype "bidirectional"))
      (node (ref "U$25") (pin "LED+") (pinfunction "LED+_LED+") (pintype "bidirectional"))
      (node (ref "U$26") (pin "LED+") (pinfunction "LED+_LED+") (pintype "bidirectional"))
      (node (ref "U$27") (pin "LED+") (pinfunction "LED+_LED+") (pintype "bidirectional"))
      (node (ref "U$28") (pin "LED+") (pinfunction "LED+_LED+") (pintype "bidirectional"))
      (node (ref "U$29") (pin "LED+") (pinfunction "LED+_LED+") (pintype "bidirectional"))
      (node (ref "U$3") (pin "LED+") (pinfunction "LED+_LED+") (pintype "bidirectional"))
      (node (ref "U$30") (pin "LED+") (pinfunction "LED+_LED+") (pintype "bidirectional"))
      (node (ref "U$31") (pin "LED+") (pinfunction "LED+_LED+") (pintype "bidirectional"))
      (node (ref "U$32") (pin "LED+") (pinfunction "LED+_LED+") (pintype "bidirectional"))
      (node (ref "U$33") (pin "LED+") (pinfunction "LED+_LED+") (pintype "bidirectional"))
      (node (ref "U$34") (pin "LED+") (pinfunction "LED+_LED+") (pintype "bidirectional"))
      (node (ref "U$35") (pin "LED+") (pinfunction "LED+_LED+") (pintype "bidirectional"))
      (node (ref "U$36") (pin "LED+") (pinfunction "LED+_LED+") (pintype "bidirectional"))
      (node (ref "U$37") (pin "LED+") (pinfunction "LED+_LED+") (pintype "bidirectional"))
      (node (ref "U$38") (pin "LED+") (pinfunction "LED+_LED+") (pintype "bidirectional"))
      (node (ref "U$39") (pin "LED+") (pinfunction "LED+_LED+") (pintype "bidirectional"))
      (node (ref "U$4") (pin "LED+") (pinfunction "LED+_LED+") (pintype "bidirectional"))
      (node (ref "U$40") (pin "LED+") (pinfunction "LED+_LED+") (pintype "bidirectional"))
      (node (ref "U$41") (pin "LED+") (pinfunction "LED+_LED+") (pintype "bidirectional"))
      (node (ref "U$42") (pin "LED+") (pinfunction "LED+_LED+") (pintype "bidirectional"))
      (node (ref "U$43") (pin "LED+") (pinfunction "LED+_LED+") (pintype "bidirectional"))
      (node (ref "U$44") (pin "LED+") (pinfunction "LED+_LED+") (pintype "bidirectional"))
      (node (ref "U$45") (pin "LED+") (pinfunction "LED+_LED+") (pintype "bidirectional"))
      (node (ref "U$46") (pin "LED+") (pinfunction "LED+_LED+") (pintype "bidirectional"))
      (node (ref "U$47") (pin "LED+") (pinfunction "LED+_LED+") (pintype "bidirectional"))
      (node (ref "U$48") (pin "LED+") (pinfunction "LED+_LED+") (pintype "bidirectional"))
      (node (ref "U$49") (pin "LED+") (pinfunction "LED+_LED+") (pintype "bidirectional"))
      (node (ref "U$5") (pin "LED+") (pinfunction "LED+_LED+") (pintype "bidirectional"))
      (node (ref "U$50") (pin "LED+") (pinfunction "LED+_LED+") (pintype "bidirectional"))
      (node (ref "U$51") (pin "LED+") (pinfunction "LED+_LED+") (pintype "bidirectional"))
      (node (ref "U$52") (pin "LED+") (pinfunction "LED+_LED+") (pintype "bidirectional"))
      (node (ref "U$53") (pin "LED+") (pinfunction "LED+_LED+") (pintype "bidirectional"))
      (node (ref "U$54") (pin "LED+") (pinfunction "LED+_LED+") (pintype "bidirectional"))
      (node (ref "U$55") (pin "LED+") (pinfunction "LED+_LED+") (pintype "bidirectional"))
      (node (ref "U$56") (pin "LED+") (pinfunction "LED+_LED+") (pintype "bidirectional"))
      (node (ref "U$57") (pin "LED+") (pinfunction "LED+_LED+") (pintype "bidirectional"))
      (node (ref "U$58") (pin "LED+") (pinfunction "LED+_LED+") (pintype "bidirectional"))
      (node (ref "U$59") (pin "LED+") (pinfunction "LED+_LED+") (pintype "bidirectional"))
      (node (ref "U$6") (pin "LED+") (pinfunction "LED+_LED+") (pintype "bidirectional"))
      (node (ref "U$60") (pin "LED+") (pinfunction "LED+_LED+") (pintype "bidirectional"))
      (node (ref "U$61") (pin "LED+") (pinfunction "LED+_LED+") (pintype "bidirectional"))
      (node (ref "U$62") (pin "LED+") (pinfunction "LED+_LED+") (pintype "bidirectional"))
      (node (ref "U$63") (pin "LED+") (pinfunction "LED+_LED+") (pintype "bidirectional"))
      (node (ref "U$64") (pin "LED+") (pinfunction "LED+_LED+") (pintype "bidirectional"))
      (node (ref "U$65") (pin "LED+") (pinfunction "LED+_LED+") (pintype "bidirectional"))
      (node (ref "U$66") (pin "LED+") (pinfunction "LED+_LED+") (pintype "bidirectional"))
      (node (ref "U$67") (pin "LED+") (pinfunction "LED+_LED+") (pintype "bidirectional"))
      (node (ref "U$68") (pin "LED+") (pinfunction "LED+_LED+") (pintype "bidirectional"))
      (node (ref "U$69") (pin "LED+") (pinfunction "LED+_LED+") (pintype "bidirectional"))
      (node (ref "U$7") (pin "LED+") (pinfunction "LED+_LED+") (pintype "bidirectional"))
      (node (ref "U$70") (pin "LED+") (pinfunction "LED+_LED+") (pintype "bidirectional"))
      (node (ref "U$71") (pin "LED+") (pinfunction "LED+_LED+") (pintype "bidirectional"))
      (node (ref "U$72") (pin "LED+") (pinfunction "LED+_LED+") (pintype "bidirectional"))
      (node (ref "U$73") (pin "LED+") (pinfunction "LED+_LED+") (pintype "bidirectional"))
      (node (ref "U$74") (pin "LED+") (pinfunction "LED+_LED+") (pintype "bidirectional"))
      (node (ref "U$75") (pin "LED+") (pinfunction "LED+_LED+") (pintype "bidirectional"))
      (node (ref "U$8") (pin "LED+") (pinfunction "LED+_LED+") (pintype "bidirectional"))
      (node (ref "U$9") (pin "LED+") (pinfunction "LED+_LED+") (pintype "bidirectional"))
    )
    (net (code "20") (name "/LED-") (class "Default")
      (node (ref "U$1") (pin "LED-") (pinfunction "LED-_LED-") (pintype "bidirectional"))
      (node (ref "U$10") (pin "LED-") (pinfunction "LED-_LED-") (pintype "bidirectional"))
      (node (ref "U$11") (pin "LED-") (pinfunction "LED-_LED-") (pintype "bidirectional"))
      (node (ref "U$12") (pin "LED-") (pinfunction "LED-_LED-") (pintype "bidirectional"))
      (node (ref "U$13") (pin "LED-") (pinfunction "LED-_LED-") (pintype "bidirectional"))
      (node (ref "U$14") (pin "LED-") (pinfunction "LED-_LED-") (pintype "bidirectional"))
      (node (ref "U$15") (pin "LED-") (pinfunction "LED-_LED-") (pintype "bidirectional"))
      (node (ref "U$16") (pin "LED-") (pinfunction "LED-_LED-") (pintype "bidirectional"))
      (node (ref "U$17") (pin "LED-") (pinfunction "LED-_LED-") (pintype "bidirectional"))
      (node (ref "U$18") (pin "LED-") (pinfunction "LED-_LED-") (pintype "bidirectional"))
      (node (ref "U$19") (pin "LED-") (pinfunction "LED-_LED-") (pintype "bidirectional"))
      (node (ref "U$2") (pin "LED-") (pinfunction "LED-_LED-") (pintype "bidirectional"))
      (node (ref "U$20") (pin "LED-") (pinfunction "LED-_LED-") (pintype "bidirectional"))
      (node (ref "U$21") (pin "LED-") (pinfunction "LED-_LED-") (pintype "bidirectional"))
      (node (ref "U$22") (pin "LED-") (pinfunction "LED-_LED-") (pintype "bidirectional"))
      (node (ref "U$23") (pin "LED-") (pinfunction "LED-_LED-") (pintype "bidirectional"))
      (node (ref "U$24") (pin "LED-") (pinfunction "LED-_LED-") (pintype "bidirectional"))
      (node (ref "U$25") (pin "LED-") (pinfunction "LED-_LED-") (pintype "bidirectional"))
      (node (ref "U$26") (pin "LED-") (pinfunction "LED-_LED-") (pintype "bidirectional"))
      (node (ref "U$27") (pin "LED-") (pinfunction "LED-_LED-") (pintype "bidirectional"))
      (node (ref "U$28") (pin "LED-") (pinfunction "LED-_LED-") (pintype "bidirectional"))
      (node (ref "U$29") (pin "LED-") (pinfunction "LED-_LED-") (pintype "bidirectional"))
      (node (ref "U$3") (pin "LED-") (pinfunction "LED-_LED-") (pintype "bidirectional"))
      (node (ref "U$30") (pin "LED-") (pinfunction "LED-_LED-") (pintype "bidirectional"))
      (node (ref "U$31") (pin "LED-") (pinfunction "LED-_LED-") (pintype "bidirectional"))
      (node (ref "U$32") (pin "LED-") (pinfunction "LED-_LED-") (pintype "bidirectional"))
      (node (ref "U$33") (pin "LED-") (pinfunction "LED-_LED-") (pintype "bidirectional"))
      (node (ref "U$34") (pin "LED-") (pinfunction "LED-_LED-") (pintype "bidirectional"))
      (node (ref "U$35") (pin "LED-") (pinfunction "LED-_LED-") (pintype "bidirectional"))
      (node (ref "U$36") (pin "LED-") (pinfunction "LED-_LED-") (pintype "bidirectional"))
      (node (ref "U$37") (pin "LED-") (pinfunction "LED-_LED-") (pintype "bidirectional"))
      (node (ref "U$38") (pin "LED-") (pinfunction "LED-_LED-") (pintype "bidirectional"))
      (node (ref "U$39") (pin "LED-") (pinfunction "LED-_LED-") (pintype "bidirectional"))
      (node (ref "U$4") (pin "LED-") (pinfunction "LED-_LED-") (pintype "bidirectional"))
      (node (ref "U$40") (pin "LED-") (pinfunction "LED-_LED-") (pintype "bidirectional"))
      (node (ref "U$41") (pin "LED-") (pinfunction "LED-_LED-") (pintype "bidirectional"))
      (node (ref "U$42") (pin "LED-") (pinfunction "LED-_LED-") (pintype "bidirectional"))
      (node (ref "U$43") (pin "LED-") (pinfunction "LED-_LED-") (pintype "bidirectional"))
      (node (ref "U$44") (pin "LED-") (pinfunction "LED-_LED-") (pintype "bidirectional"))
      (node (ref "U$45") (pin "LED-") (pinfunction "LED-_LED-") (pintype "bidirectional"))
      (node (ref "U$46") (pin "LED-") (pinfunction "LED-_LED-") (pintype "bidirectional"))
      (node (ref "U$47") (pin "LED-") (pinfunction "LED-_LED-") (pintype "bidirectional"))
      (node (ref "U$48") (pin "LED-") (pinfunction "LED-_LED-") (pintype "bidirectional"))
      (node (ref "U$49") (pin "LED-") (pinfunction "LED-_LED-") (pintype "bidirectional"))
      (node (ref "U$5") (pin "LED-") (pinfunction "LED-_LED-") (pintype "bidirectional"))
      (node (ref "U$50") (pin "LED-") (pinfunction "LED-_LED-") (pintype "bidirectional"))
      (node (ref "U$51") (pin "LED-") (pinfunction "LED-_LED-") (pintype "bidirectional"))
      (node (ref "U$53") (pin "LED-") (pinfunction "LED-_LED-") (pintype "bidirectional"))
      (node (ref "U$54") (pin "LED-") (pinfunction "LED-_LED-") (pintype "bidirectional"))
      (node (ref "U$55") (pin "LED-") (pinfunction "LED-_LED-") (pintype "bidirectional"))
      (node (ref "U$56") (pin "LED-") (pinfunction "LED-_LED-") (pintype "bidirectional"))
      (node (ref "U$57") (pin "LED-") (pinfunction "LED-_LED-") (pintype "bidirectional"))
      (node (ref "U$58") (pin "LED-") (pinfunction "LED-_LED-") (pintype "bidirectional"))
      (node (ref "U$59") (pin "LED-") (pinfunction "LED-_LED-") (pintype "bidirectional"))
      (node (ref "U$6") (pin "LED-") (pinfunction "LED-_LED-") (pintype "bidirectional"))
      (node (ref "U$60") (pin "LED-") (pinfunction "LED-_LED-") (pintype "bidirectional"))
      (node (ref "U$61") (pin "LED-") (pinfunction "LED-_LED-") (pintype "bidirectional"))
      (node (ref "U$62") (pin "LED-") (pinfunction "LED-_LED-") (pintype "bidirectional"))
      (node (ref "U$63") (pin "LED-") (pinfunction "LED-_LED-") (pintype "bidirectional"))
      (node (ref "U$64") (pin "LED-") (pinfunction "LED-_LED-") (pintype "bidirectional"))
      (node (ref "U$65") (pin "LED-") (pinfunction "LED-_LED-") (pintype "bidirectional"))
      (node (ref "U$66") (pin "LED-") (pinfunction "LED-_LED-") (pintype "bidirectional"))
      (node (ref "U$67") (pin "LED-") (pinfunction "LED-_LED-") (pintype "bidirectional"))
      (node (ref "U$68") (pin "LED-") (pinfunction "LED-_LED-") (pintype "bidirectional"))
      (node (ref "U$69") (pin "LED-") (pinfunction "LED-_LED-") (pintype "bidirectional"))
      (node (ref "U$7") (pin "LED-") (pinfunction "LED-_LED-") (pintype "bidirectional"))
      (node (ref "U$71") (pin "LED-") (pinfunction "LED-_LED-") (pintype "bidirectional"))
      (node (ref "U$72") (pin "LED-") (pinfunction "LED-_LED-") (pintype "bidirectional"))
      (node (ref "U$73") (pin "LED-") (pinfunction "LED-_LED-") (pintype "bidirectional"))
      (node (ref "U$74") (pin "LED-") (pinfunction "LED-_LED-") (pintype "bidirectional"))
      (node (ref "U$75") (pin "LED-") (pinfunction "LED-_LED-") (pintype "bidirectional"))
      (node (ref "U$8") (pin "LED-") (pinfunction "LED-_LED-") (pintype "bidirectional"))
      (node (ref "U$9") (pin "LED-") (pinfunction "LED-_LED-") (pintype "bidirectional"))
    )
    (net (code "21") (name "/LED-\\") (class "Default")
      (node (ref "U$70") (pin "LED-") (pinfunction "LED-_LED-") (pintype "bidirectional"))
    )
    (net (code "22") (name "/MISO") (class "Default")
      (node (ref "IC1") (pin "7") (pinfunction "PB6_(MISO)_7") (pintype "bidirectional"))
      (node (ref "ISP1") (pin "1") (pinfunction "MISO_1") (pintype "input"))
    )
    (net (code "23") (name "/MOSI") (class "Default")
      (node (ref "IC1") (pin "6") (pinfunction "PB5_(MOSI)_6") (pintype "bidirectional"))
      (node (ref "ISP1") (pin "4") (pinfunction "MOSI_4") (pintype "output"))
    )
    (net (code "24") (name "/N$119") (class "Default")
      (node (ref "U$52") (pin "LED-") (pinfunction "LED-_LED-") (pintype "bidirectional"))
    )
    (net (code "25") (name "/RESET") (class "Default")
      (node (ref "IC1") (pin "9") (pinfunction "~{RESET}_9") (pintype "bidirectional"))
      (node (ref "ISP1") (pin "5") (pinfunction "RST_5") (pintype "output"))
      (node (ref "R1") (pin "1") (pinfunction "1_1") (pintype "passive"))
      (node (ref "S1") (pin "3") (pinfunction "3_3") (pintype "passive"))
    )
    (net (code "26") (name "/RGB_DATA") (class "Default")
      (node (ref "IC1") (pin "27") (pinfunction "PC5_(TDI)_27") (pintype "bidirectional"))
      (node (ref "LED1") (pin "4") (pinfunction "DI_4") (pintype "bidirectional"))
    )
    (net (code "27") (name "/ROW0") (class "Default")
      (node (ref "IC1") (pin "1") (pinfunction "PB0_(XCK/T0)_1") (pintype "bidirectional"))
      (node (ref "U$1") (pin "UP") (pinfunction "UP_UP") (pintype "bidirectional"))
      (node (ref "U$10") (pin "UP") (pinfunction "UP_UP") (pintype "bidirectional"))
      (node (ref "U$11") (pin "UP") (pinfunction "UP_UP") (pintype "bidirectional"))
      (node (ref "U$12") (pin "UP") (pinfunction "UP_UP") (pintype "bidirectional"))
      (node (ref "U$13") (pin "UP") (pinfunction "UP_UP") (pintype "bidirectional"))
      (node (ref "U$14") (pin "UP") (pinfunction "UP_UP") (pintype "bidirectional"))
      (node (ref "U$15") (pin "UP") (pinfunction "UP_UP") (pintype "bidirectional"))
      (node (ref "U$2") (pin "UP") (pinfunction "UP_UP") (pintype "bidirectional"))
      (node (ref "U$3") (pin "UP") (pinfunction "UP_UP") (pintype "bidirectional"))
      (node (ref "U$4") (pin "UP") (pinfunction "UP_UP") (pintype "bidirectional"))
      (node (ref "U$5") (pin "UP") (pinfunction "UP_UP") (pintype "bidirectional"))
      (node (ref "U$6") (pin "UP") (pinfunction "UP_UP") (pintype "bidirectional"))
      (node (ref "U$7") (pin "UP") (pinfunction "UP_UP") (pintype "bidirectional"))
      (node (ref "U$8") (pin "UP") (pinfunction "UP_UP") (pintype "bidirectional"))
      (node (ref "U$9") (pin "UP") (pinfunction "UP_UP") (pintype "bidirectional"))
    )
    (net (code "28") (name "/ROW1") (class "Default")
      (node (ref "IC1") (pin "2") (pinfunction "PB1_(T1)_2") (pintype "bidirectional"))
      (node (ref "U$16") (pin "UP") (pinfunction "UP_UP") (pintype "bidirectional"))
      (node (ref "U$17") (pin "UP") (pinfunction "UP_UP") (pintype "bidirectional"))
      (node (ref "U$18") (pin "UP") (pinfunction "UP_UP") (pintype "bidirectional"))
      (node (ref "U$19") (pin "UP") (pinfunction "UP_UP") (pintype "bidirectional"))
      (node (ref "U$20") (pin "UP") (pinfunction "UP_UP") (pintype "bidirectional"))
      (node (ref "U$21") (pin "UP") (pinfunction "UP_UP") (pintype "bidirectional"))
      (node (ref "U$22") (pin "UP") (pinfunction "UP_UP") (pintype "bidirectional"))
      (node (ref "U$23") (pin "UP") (pinfunction "UP_UP") (pintype "bidirectional"))
      (node (ref "U$24") (pin "UP") (pinfunction "UP_UP") (pintype "bidirectional"))
      (node (ref "U$25") (pin "UP") (pinfunction "UP_UP") (pintype "bidirectional"))
      (node (ref "U$26") (pin "UP") (pinfunction "UP_UP") (pintype "bidirectional"))
      (node (ref "U$27") (pin "UP") (pinfunction "UP_UP") (pintype "bidirectional"))
      (node (ref "U$28") (pin "UP") (pinfunction "UP_UP") (pintype "bidirectional"))
      (node (ref "U$29") (pin "UP") (pinfunction "UP_UP") (pintype "bidirectional"))
      (node (ref "U$30") (pin "UP") (pinfunction "UP_UP") (pintype "bidirectional"))
    )
    (net (code "29") (name "/ROW2") (class "Default")
      (node (ref "IC1") (pin "3") (pinfunction "PB2_(AIN0/INT2)_3") (pintype "bidirectional"))
      (node (ref "U$31") (pin "UP") (pinfunction "UP_UP") (pintype "bidirectional"))
      (node (ref "U$32") (pin "UP") (pinfunction "UP_UP") (pintype "bidirectional"))
      (node (ref "U$33") (pin "UP") (pinfunction "UP_UP") (pintype "bidirectional"))
      (node (ref "U$34") (pin "UP") (pinfunction "UP_UP") (pintype "bidirectional"))
      (node (ref "U$35") (pin "UP") (pinfunction "UP_UP") (pintype "bidirectional"))
      (node (ref "U$36") (pin "UP") (pinfunction "UP_UP") (pintype "bidirectional"))
      (node (ref "U$37") (pin "UP") (pinfunction "UP_UP") (pintype "bidirectional"))
      (node (ref "U$38") (pin "UP") (pinfunction "UP_UP") (pintype "bidirectional"))
      (node (ref "U$39") (pin "UP") (pinfunction "UP_UP") (pintype "bidirectional"))
      (node (ref "U$40") (pin "UP") (pinfunction "UP_UP") (pintype "bidirectional"))
      (node (ref "U$41") (pin "UP") (pinfunction "UP_UP") (pintype "bidirectional"))
      (node (ref "U$42") (pin "UP") (pinfunction "UP_UP") (pintype "bidirectional"))
      (node (ref "U$43") (pin "UP") (pinfunction "UP_UP") (pintype "bidirectional"))
      (node (ref "U$44") (pin "UP") (pinfunction "UP_UP") (pintype "bidirectional"))
      (node (ref "U$45") (pin "UP") (pinfunction "UP_UP") (pintype "bidirectional"))
    )
    (net (code "30") (name "/ROW3") (class "Default")
      (node (ref "IC1") (pin "4") (pinfunction "PB3_(AIN1/OC0)_4") (pintype "bidirectional"))
      (node (ref "U$46") (pin "UP") (pinfunction "UP_UP") (pintype "bidirectional"))
      (node (ref "U$47") (pin "UP") (pinfunction "UP_UP") (pintype "bidirectional"))
      (node (ref "U$48") (pin "UP") (pinfunction "UP_UP") (pintype "bidirectional"))
      (node (ref "U$49") (pin "UP") (pinfunction "UP_UP") (pintype "bidirectional"))
      (node (ref "U$50") (pin "UP") (pinfunction "UP_UP") (pintype "bidirectional"))
      (node (ref "U$51") (pin "UP") (pinfunction "UP_UP") (pintype "bidirectional"))
      (node (ref "U$52") (pin "UP") (pinfunction "UP_UP") (pintype "bidirectional"))
      (node (ref "U$53") (pin "UP") (pinfunction "UP_UP") (pintype "bidirectional"))
      (node (ref "U$54") (pin "UP") (pinfunction "UP_UP") (pintype "bidirectional"))
      (node (ref "U$55") (pin "UP") (pinfunction "UP_UP") (pintype "bidirectional"))
      (node (ref "U$56") (pin "UP") (pinfunction "UP_UP") (pintype "bidirectional"))
      (node (ref "U$57") (pin "UP") (pinfunction "UP_UP") (pintype "bidirectional"))
      (node (ref "U$58") (pin "UP") (pinfunction "UP_UP") (pintype "bidirectional"))
      (node (ref "U$59") (pin "UP") (pinfunction "UP_UP") (pintype "bidirectional"))
      (node (ref "U$60") (pin "UP") (pinfunction "UP_UP") (pintype "bidirectional"))
    )
    (net (code "31") (name "/ROW4") (class "Default")
      (node (ref "IC1") (pin "5") (pinfunction "PB4_(~{SS})_5") (pintype "bidirectional"))
      (node (ref "U$61") (pin "UP") (pinfunction "UP_UP") (pintype "bidirectional"))
      (node (ref "U$62") (pin "UP") (pinfunction "UP_UP") (pintype "bidirectional"))
      (node (ref "U$63") (pin "UP") (pinfunction "UP_UP") (pintype "bidirectional"))
      (node (ref "U$64") (pin "UP") (pinfunction "UP_UP") (pintype "bidirectional"))
      (node (ref "U$65") (pin "UP") (pinfunction "UP_UP") (pintype "bidirectional"))
      (node (ref "U$66") (pin "UP") (pinfunction "UP_UP") (pintype "bidirectional"))
      (node (ref "U$67") (pin "UP") (pinfunction "UP_UP") (pintype "bidirectional"))
      (node (ref "U$68") (pin "UP") (pinfunction "UP_UP") (pintype "bidirectional"))
      (node (ref "U$69") (pin "UP") (pinfunction "UP_UP") (pintype "bidirectional"))
      (node (ref "U$70") (pin "UP") (pinfunction "UP_UP") (pintype "bidirectional"))
      (node (ref "U$71") (pin "UP") (pinfunction "UP_UP") (pintype "bidirectional"))
      (node (ref "U$72") (pin "UP") (pinfunction "UP_UP") (pintype "bidirectional"))
      (node (ref "U$73") (pin "UP") (pinfunction "UP_UP") (pintype "bidirectional"))
      (node (ref "U$74") (pin "UP") (pinfunction "UP_UP") (pintype "bidirectional"))
      (node (ref "U$75") (pin "UP") (pinfunction "UP_UP") (pintype "bidirectional"))
    )
    (net (code "32") (name "/SCK") (class "Default")
      (node (ref "IC1") (pin "8") (pinfunction "PB7_(SCK)_8") (pintype "bidirectional"))
      (node (ref "ISP1") (pin "3") (pinfunction "SCK_3") (pintype "output"))
    )
    (net (code "33") (name "/USB_D+") (class "Default")
      (node (ref "IC1") (pin "16") (pinfunction "PD2_(INT0)_16") (pintype "bidirectional"))
      (node (ref "R6") (pin "2") (pinfunction "2_2") (pintype "passive"))
    )
    (net (code "34") (name "/USB_D-") (class "Default")
      (node (ref "IC1") (pin "17") (pinfunction "PD3_(INT1)_17") (pintype "bidirectional"))
      (node (ref "R5") (pin "2") (pinfunction "2_2") (pintype "passive"))
    )
    (net (code "35") (name "Net-(F1-2)") (class "Default")
      (node (ref "F1") (pin "P$2") (pinfunction "2_P$2") (pintype "bidirectional"))
      (node (ref "J1") (pin "A4") (pinfunction "VBUS_A4") (pintype "power_in"))
      (node (ref "J1") (pin "A9") (pinfunction "VBUS_A9") (pintype "power_in"))
      (node (ref "J1") (pin "B4") (pinfunction "VBUS_B4") (pintype "power_in"))
      (node (ref "J1") (pin "B9") (pinfunction "VBUS_B9") (pintype "power_in"))
    )
    (net (code "36") (name "Net-(IC1-XTAL1)") (class "Default")
      (node (ref "C2") (pin "2") (pinfunction "2_2") (pintype "passive"))
      (node (ref "IC1") (pin "13") (pinfunction "XTAL1_13") (pintype "bidirectional"))
      (node (ref "X1") (pin "1") (pinfunction "1_1") (pintype "passive"))
    )
    (net (code "37") (name "Net-(IC1-XTAL2)") (class "Default")
      (node (ref "C1") (pin "2") (pinfunction "2_2") (pintype "passive"))
      (node (ref "IC1") (pin "12") (pinfunction "XTAL2_12") (pintype "bidirectional"))
      (node (ref "X1") (pin "2") (pinfunction "2_2") (pintype "passive"))
    )
    (net (code "38") (name "Net-(J1-CC1)") (class "Default")
      (node (ref "J1") (pin "A5") (pinfunction "CC1_A5") (pintype "bidirectional"))
      (node (ref "R3") (pin "1") (pinfunction "1_1") (pintype "passive"))
    )
    (net (code "39") (name "Net-(J1-CC2)") (class "Default")
      (node (ref "J1") (pin "B5") (pinfunction "CC2_B5") (pintype "bidirectional"))
      (node (ref "R4") (pin "1") (pinfunction "1_1") (pintype "passive"))
    )
    (net (code "40") (name "Net-(J1-DN1)") (class "Default")
      (node (ref "D76") (pin "C") (pinfunction "C_C") (pintype "passive"))
      (node (ref "J1") (pin "A7") (pinfunction "DN1_A7") (pintype "bidirectional"))
      (node (ref "J1") (pin "B7") (pinfunction "DN2_B7") (pintype "bidirectional"))
      (node (ref "R5") (pin "1") (pinfunction "1_1") (pintype "passive"))
      (node (ref "R7") (pin "1") (pinfunction "1_1") (pintype "passive"))
    )
    (net (code "41") (name "Net-(J1-DP1)") (class "Default")
      (node (ref "D77") (pin "C") (pinfunction "C_C") (pintype "passive"))
      (node (ref "J1") (pin "A6") (pinfunction "DP1_A6") (pintype "bidirectional"))
      (node (ref "J1") (pin "B6") (pinfunction "DP2_B6") (pintype "bidirectional"))
      (node (ref "R6") (pin "1") (pinfunction "1_1") (pintype "passive"))
    )
    (net (code "42") (name "Net-(J1-GND-PadA1)") (class "Default")
      (node (ref "J1") (pin "A1") (pinfunction "GND_A1") (pintype "passive"))
      (node (ref "J1") (pin "A12") (pinfunction "GND_A12") (pintype "passive"))
      (node (ref "J1") (pin "B1") (pinfunction "GND_B1") (pintype "passive"))
      (node (ref "J1") (pin "B12") (pinfunction "GND_B12") (pintype "passive"))
    )
    (net (code "43") (name "Net-(J1-SHELL-PadP1)") (class "Default")
      (node (ref "J1") (pin "P1") (pinfunction "SHELL_P1") (pintype "passive"))
      (node (ref "J1") (pin "P2") (pinfunction "SHELL_P2") (pintype "passive"))
      (node (ref "J1") (pin "P3") (pinfunction "SHELL_P3") (pintype "passive"))
      (node (ref "J1") (pin "P4") (pinfunction "SHELL_P4") (pintype "passive"))
    )
    (net (code "44") (name "Net-(LED1-DO)") (class "Default")
      (node (ref "LED1") (pin "2") (pinfunction "DO_2") (pintype "bidirectional"))
      (node (ref "LED2") (pin "4") (pinfunction "DI_4") (pintype "bidirectional"))
    )
    (net (code "45") (name "Net-(LED2-DO)") (class "Default")
      (node (ref "LED2") (pin "2") (pinfunction "DO_2") (pintype "bidirectional"))
      (node (ref "LED3") (pin "4") (pinfunction "DI_4") (pintype "bidirectional"))
    )
    (net (code "46") (name "Net-(LED3-DO)") (class "Default")
      (node (ref "LED3") (pin "2") (pinfunction "DO_2") (pintype "bidirectional"))
      (node (ref "LED4") (pin "4") (pinfunction "DI_4") (pintype "bidirectional"))
    )
    (net (code "47") (name "Net-(LED4-DO)") (class "Default")
      (node (ref "LED4") (pin "2") (pinfunction "DO_2") (pintype "bidirectional"))
      (node (ref "LED5") (pin "4") (pinfunction "DI_4") (pintype "bidirectional"))
    )
    (net (code "48") (name "Net-(LED5-DO)") (class "Default")
      (node (ref "LED5") (pin "2") (pinfunction "DO_2") (pintype "bidirectional"))
      (node (ref "LED6") (pin "4") (pinfunction "DI_4") (pintype "bidirectional"))
    )
    (net (code "49") (name "Net-(LED6-DO)") (class "Default")
      (node (ref "LED6") (pin "2") (pinfunction "DO_2") (pintype "bidirectional"))
      (node (ref "LED7") (pin "4") (pinfunction "DI_4") (pintype "bidirectional"))
    )
    (net (code "50") (name "Net-(LED7-DO)") (class "Default")
      (node (ref "LED7") (pin "2") (pinfunction "DO_2") (pintype "bidirectional"))
      (node (ref "LED8") (pin "4") (pinfunction "DI_4") (pintype "bidirectional"))
    )
    (net (code "51") (name "Net-(LED8-DO)") (class "Default")
      (node (ref "LED8") (pin "2") (pinfunction "DO_2") (pintype "bidirectional"))
      (node (ref "LED9") (pin "4") (pinfunction "DI_4") (pintype "bidirectional"))
    )
    (net (code "52") (name "Net-(LED10-DI)") (class "Default")
      (node (ref "LED10") (pin "4") (pinfunction "DI_4") (pintype "bidirectional"))
      (node (ref "LED9") (pin "2") (pinfunction "DO_2") (pintype "bidirectional"))
    )
    (net (code "53") (name "Net-(LED10-DO)") (class "Default")
      (node (ref "LED10") (pin "2") (pinfunction "DO_2") (pintype "bidirectional"))
      (node (ref "LED11") (pin "4") (pinfunction "DI_4") (pintype "bidirectional"))
    )
    (net (code "54") (name "Net-(LED11-DO)") (class "Default")
      (node (ref "LED11") (pin "2") (pinfunction "DO_2") (pintype "bidirectional"))
      (node (ref "LED12") (pin "4") (pinfunction "DI_4") (pintype "bidirectional"))
    )
    (net (code "55") (name "Net-(LED12-DO)") (class "Default")
      (node (ref "LED12") (pin "2") (pinfunction "DO_2") (pintype "bidirectional"))
      (node (ref "LED13") (pin "4") (pinfunction "DI_4") (pintype "bidirectional"))
    )
    (net (code "56") (name "Net-(LED13-DO)") (class "Default")
      (node (ref "LED13") (pin "2") (pinfunction "DO_2") (pintype "bidirectional"))
      (node (ref "LED14") (pin "4") (pinfunction "DI_4") (pintype "bidirectional"))
    )
    (net (code "57") (name "Net-(LED15-C)") (class "Default")
      (node (ref "LED15") (pin "K") (pinfunction "C_K") (pintype "passive"))
      (node (ref "R2") (pin "1") (pinfunction "1_1") (pintype "passive"))
    )
    (net (code "58") (name "Net-(U$1-A)") (class "Default")
      (node (ref "D1") (pin "A") (pinfunction "A_A") (pintype "passive"))
      (node (ref "U$1") (pin "SIDE") (pinfunction "A_SIDE") (pintype "bidirectional"))
    )
    (net (code "59") (name "Net-(U$2-A)") (class "Default")
      (node (ref "D2") (pin "A") (pinfunction "A_A") (pintype "passive"))
      (node (ref "U$2") (pin "SIDE") (pinfunction "A_SIDE") (pintype "bidirectional"))
    )
    (net (code "60") (name "Net-(U$3-A)") (class "Default")
      (node (ref "D3") (pin "A") (pinfunction "A_A") (pintype "passive"))
      (node (ref "U$3") (pin "SIDE") (pinfunction "A_SIDE") (pintype "bidirectional"))
    )
    (net (code "61") (name "Net-(U$4-A)") (class "Default")
      (node (ref "D4") (pin "A") (pinfunction "A_A") (pintype "passive"))
      (node (ref "U$4") (pin "SIDE") (pinfunction "A_SIDE") (pintype "bidirectional"))
    )
    (net (code "62") (name "Net-(U$5-A)") (class "Default")
      (node (ref "D5") (pin "A") (pinfunction "A_A") (pintype "passive"))
      (node (ref "U$5") (pin "SIDE") (pinfunction "A_SIDE") (pintype "bidirectional"))
    )
    (net (code "63") (name "Net-(U$6-A)") (class "Default")
      (node (ref "D6") (pin "A") (pinfunction "A_A") (pintype "passive"))
      (node (ref "U$6") (pin "SIDE") (pinfunction "A_SIDE") (pintype "bidirectional"))
    )
    (net (code "64") (name "Net-(U$7-A)") (class "Default")
      (node (ref "D7") (pin "A") (pinfunction "A_A") (pintype "passive"))
      (node (ref "U$7") (pin "SIDE") (pinfunction "A_SIDE") (pintype "bidirectional"))
    )
    (net (code "65") (name "Net-(U$8-A)") (class "Default")
      (node (ref "D8") (pin "A") (pinfunction "A_A") (pintype "passive"))
      (node (ref "U$8") (pin "SIDE") (pinfunction "A_SIDE") (pintype "bidirectional"))
    )
    (net (code "66") (name "Net-(U$9-A)") (class "Default")
      (node (ref "D9") (pin "A") (pinfunction "A_A") (pintype "passive"))
      (node (ref "U$9") (pin "SIDE") (pinfunction "A_SIDE") (pintype "bidirectional"))
    )
    (net (code "67") (name "Net-(U$10-A)") (class "Default")
      (node (ref "D10") (pin "A") (pinfunction "A_A") (pintype "passive"))
      (node (ref "U$10") (pin "SIDE") (pinfunction "A_SIDE") (pintype "bidirectional"))
    )
    (net (code "68") (name "Net-(U$11-A)") (class "Default")
      (node (ref "D11") (pin "A") (pinfunction "A_A") (pintype "passive"))
      (node (ref "U$11") (pin "SIDE") (pinfunction "A_SIDE") (pintype "bidirectional"))
    )
    (net (code "69") (name "Net-(U$12-A)") (class "Default")
      (node (ref "D12") (pin "A") (pinfunction "A_A") (pintype "passive"))
      (node (ref "U$12") (pin "SIDE") (pinfunction "A_SIDE") (pintype "bidirectional"))
    )
    (net (code "70") (name "Net-(U$13-A)") (class "Default")
      (node (ref "D13") (pin "A") (pinfunction "A_A") (pintype "passive"))
      (node (ref "U$13") (pin "SIDE") (pinfunction "A_SIDE") (pintype "bidirectional"))
    )
    (net (code "71") (name "Net-(U$14-A)") (class "Default")
      (node (ref "D14") (pin "A") (pinfunction "A_A") (pintype "passive"))
      (node (ref "U$14") (pin "SIDE") (pinfunction "A_SIDE") (pintype "bidirectional"))
    )
    (net (code "72") (name "Net-(U$15-A)") (class "Default")
      (node (ref "D15") (pin "A") (pinfunction "A_A") (pintype "passive"))
      (node (ref "U$15") (pin "SIDE") (pinfunction "A_SIDE") (pintype "bidirectional"))
    )
    (net (code "73") (name "Net-(U$16-A)") (class "Default")
      (node (ref "D16") (pin "A") (pinfunction "A_A") (pintype "passive"))
      (node (ref "U$16") (pin "SIDE") (pinfunction "A_SIDE") (pintype "bidirectional"))
    )
    (net (code "74") (name "Net-(U$17-A)") (class "Default")
      (node (ref "D17") (pin "A") (pinfunction "A_A") (pintype "passive"))
      (node (ref "U$17") (pin "SIDE") (pinfunction "A_SIDE") (pintype "bidirectional"))
    )
    (net (code "75") (name "Net-(U$18-A)") (class "Default")
      (node (ref "D18") (pin "A") (pinfunction "A_A") (pintype "passive"))
      (node (ref "U$18") (pin "SIDE") (pinfunction "A_SIDE") (pintype "bidirectional"))
    )
    (net (code "76") (name "Net-(U$19-A)") (class "Default")
      (node (ref "D19") (pin "A") (pinfunction "A_A") (pintype "passive"))
      (node (ref "U$19") (pin "SIDE") (pinfunction "A_SIDE") (pintype "bidirectional"))
    )
    (net (code "77") (name "Net-(U$20-A)") (class "Default")
      (node (ref "D20") (pin "A") (pinfunction "A_A") (pintype "passive"))
      (node (ref "U$20") (pin "SIDE") (pinfunction "A_SIDE") (pintype "bidirectional"))
    )
    (net (code "78") (name "Net-(U$21-A)") (class "Default")
      (node (ref "D21") (pin "A") (pinfunction "A_A") (pintype "passive"))
      (node (ref "U$21") (pin "SIDE") (pinfunction "A_SIDE") (pintype "bidirectional"))
    )
    (net (code "79") (name "Net-(U$22-A)") (class "Default")
      (node (ref "D22") (pin "A") (pinfunction "A_A") (pintype "passive"))
      (node (ref "U$22") (pin "SIDE") (pinfunction "A_SIDE") (pintype "bidirectional"))
    )
    (net (code "80") (name "Net-(U$23-A)") (class "Default")
      (node (ref "D23") (pin "A") (pinfunction "A_A") (pintype "passive"))
      (node (ref "U$23") (pin "SIDE") (pinfunction "A_SIDE") (pintype "bidirectional"))
    )
    (net (code "81") (name "Net-(U$24-A)") (class "Default")
      (node (ref "D24") (pin "A") (pinfunction "A_A") (pintype "passive"))
      (node (ref "U$24") (pin "SIDE") (pinfunction "A_SIDE") (pintype "bidirectional"))
    )
    (net (code "82") (name "Net-(U$25-A)") (class "Default")
      (node (ref "D25") (pin "A") (pinfunction "A_A") (pintype "passive"))
      (node (ref "U$25") (pin "SIDE") (pinfunction "A_SIDE") (pintype "bidirectional"))
    )
    (net (code "83") (name "Net-(U$26-A)") (class "Default")
      (node (ref "D26") (pin "A") (pinfunction "A_A") (pintype "passive"))
      (node (ref "U$26") (pin "SIDE") (pinfunction "A_SIDE") (pintype "bidirectional"))
    )
    (net (code "84") (name "Net-(U$27-A)") (class "Default")
      (node (ref "D27") (pin "A") (pinfunction "A_A") (pintype "passive"))
      (node (ref "U$27") (pin "SIDE") (pinfunction "A_SIDE") (pintype "bidirectional"))
    )
    (net (code "85") (name "Net-(U$28-A)") (class "Default")
      (node (ref "D28") (pin "A") (pinfunction "A_A") (pintype "passive"))
      (node (ref "U$28") (pin "SIDE") (pinfunction "A_SIDE") (pintype "bidirectional"))
    )
    (net (code "86") (name "Net-(U$29-A)") (class "Default")
      (node (ref "D29") (pin "A") (pinfunction "A_A") (pintype "passive"))
      (node (ref "U$29") (pin "SIDE") (pinfunction "A_SIDE") (pintype "bidirectional"))
    )
    (net (code "87") (name "Net-(U$30-A)") (class "Default")
      (node (ref "D30") (pin "A") (pinfunction "A_A") (pintype "passive"))
      (node (ref "U$30") (pin "SIDE") (pinfunction "A_SIDE") (pintype "bidirectional"))
    )
    (net (code "88") (name "Net-(U$31-A)") (class "Default")
      (node (ref "D31") (pin "A") (pinfunction "A_A") (pintype "passive"))
      (node (ref "U$31") (pin "SIDE") (pinfunction "A_SIDE") (pintype "bidirectional"))
    )
    (net (code "89") (name "Net-(U$32-A)") (class "Default")
      (node (ref "D32") (pin "A") (pinfunction "A_A") (pintype "passive"))
      (node (ref "U$32") (pin "SIDE") (pinfunction "A_SIDE") (pintype "bidirectional"))
    )
    (net (code "90") (name "Net-(U$33-A)") (class "Default")
      (node (ref "D33") (pin "A") (pinfunction "A_A") (pintype "passive"))
      (node (ref "U$33") (pin "SIDE") (pinfunction "A_SIDE") (pintype "bidirectional"))
    )
    (net (code "91") (name "Net-(U$34-A)") (class "Default")
      (node (ref "D34") (pin "A") (pinfunction "A_A") (pintype "passive"))
      (node (ref "U$34") (pin "SIDE") (pinfunction "A_SIDE") (pintype "bidirectional"))
    )
    (net (code "92") (name "Net-(U$35-A)") (class "Default")
      (node (ref "D35") (pin "A") (pinfunction "A_A") (pintype "passive"))
      (node (ref "U$35") (pin "SIDE") (pinfunction "A_SIDE") (pintype "bidirectional"))
    )
    (net (code "93") (name "Net-(U$36-A)") (class "Default")
      (node (ref "D36") (pin "A") (pinfunction "A_A") (pintype "passive"))
      (node (ref "U$36") (pin "SIDE") (pinfunction "A_SIDE") (pintype "bidirectional"))
    )
    (net (code "94") (name "Net-(U$37-A)") (class "Default")
      (node (ref "D37") (pin "A") (pinfunction "A_A") (pintype "passive"))
      (node (ref "U$37") (pin "SIDE") (pinfunction "A_SIDE") (pintype "bidirectional"))
    )
    (net (code "95") (name "Net-(U$38-A)") (class "Default")
      (node (ref "D38") (pin "A") (pinfunction "A_A") (pintype "passive"))
      (node (ref "U$38") (pin "SIDE") (pinfunction "A_SIDE") (pintype "bidirectional"))
    )
    (net (code "96") (name "Net-(U$39-A)") (class "Default")
      (node (ref "D39") (pin "A") (pinfunction "A_A") (pintype "passive"))
      (node (ref "U$39") (pin "SIDE") (pinfunction "A_SIDE") (pintype "bidirectional"))
    )
    (net (code "97") (name "Net-(U$40-A)") (class "Default")
      (node (ref "D40") (pin "A") (pinfunction "A_A") (pintype "passive"))
      (node (ref "U$40") (pin "SIDE") (pinfunction "A_SIDE") (pintype "bidirectional"))
    )
    (net (code "98") (name "Net-(U$41-A)") (class "Default")
      (node (ref "D41") (pin "A") (pinfunction "A_A") (pintype "passive"))
      (node (ref "U$41") (pin "SIDE") (pinfunction "A_SIDE") (pintype "bidirectional"))
    )
    (net (code "99") (name "Net-(U$42-A)") (class "Default")
      (node (ref "D42") (pin "A") (pinfunction "A_A") (pintype "passive"))
      (node (ref "U$42") (pin "SIDE") (pinfunction "A_SIDE") (pintype "bidirectional"))
    )
    (net (code "100") (name "Net-(U$43-A)") (class "Default")
      (node (ref "D43") (pin "A") (pinfunction "A_A") (pintype "passive"))
      (node (ref "U$43") (pin "SIDE") (pinfunction "A_SIDE") (pintype "bidirectional"))
    )
    (net (code "101") (name "Net-(U$44-A)") (class "Default")
      (node (ref "D44") (pin "A") (pinfunction "A_A") (pintype "passive"))
      (node (ref "U$44") (pin "SIDE") (pinfunction "A_SIDE") (pintype "bidirectional"))
    )
    (net (code "102") (name "Net-(U$45-A)") (class "Default")
      (node (ref "D45") (pin "A") (pinfunction "A_A") (pintype "passive"))
      (node (ref "U$45") (pin "SIDE") (pinfunction "A_SIDE") (pintype "bidirectional"))
    )
    (net (code "103") (name "Net-(U$46-A)") (class "Default")
      (node (ref "D46") (pin "A") (pinfunction "A_A") (pintype "passive"))
      (node (ref "U$46") (pin "SIDE") (pinfunction "A_SIDE") (pintype "bidirectional"))
    )
    (net (code "104") (name "Net-(U$47-A)") (class "Default")
      (node (ref "D47") (pin "A") (pinfunction "A_A") (pintype "passive"))
      (node (ref "U$47") (pin "SIDE") (pinfunction "A_SIDE") (pintype "bidirectional"))
    )
    (net (code "105") (name "Net-(U$48-A)") (class "Default")
      (node (ref "D48") (pin "A") (pinfunction "A_A") (pintype "passive"))
      (node (ref "U$48") (pin "SIDE") (pinfunction "A_SIDE") (pintype "bidirectional"))
    )
    (net (code "106") (name "Net-(U$49-A)") (class "Default")
      (node (ref "D49") (pin "A") (pinfunction "A_A") (pintype "passive"))
      (node (ref "U$49") (pin "SIDE") (pinfunction "A_SIDE") (pintype "bidirectional"))
    )
    (net (code "107") (name "Net-(U$50-A)") (class "Default")
      (node (ref "D50") (pin "A") (pinfunction "A_A") (pintype "passive"))
      (node (ref "U$50") (pin "SIDE") (pinfunction "A_SIDE") (pintype "bidirectional"))
    )
    (net (code "108") (name "Net-(U$51-A)") (class "Default")
      (node (ref "D51") (pin "A") (pinfunction "A_A") (pintype "passive"))
      (node (ref "U$51") (pin "SIDE") (pinfunction "A_SIDE") (pintype "bidirectional"))
    )
    (net (code "109") (name "Net-(U$52-A)") (class "Default")
      (node (ref "D52") (pin "A") (pinfunction "A_A") (pintype "passive"))
      (node (ref "U$52") (pin "SIDE") (pinfunction "A_SIDE") (pintype "bidirectional"))
    )
    (net (code "110") (name "Net-(U$53-A)") (class "Default")
      (node (ref "D53") (pin "A") (pinfunction "A_A") (pintype "passive"))
      (node (ref "U$53") (pin "SIDE") (pinfunction "A_SIDE") (pintype "bidirectional"))
    )
    (net (code "111") (name "Net-(U$54-A)") (class "Default")
      (node (ref "D54") (pin "A") (pinfunction "A_A") (pintype "passive"))
      (node (ref "U$54") (pin "SIDE") (pinfunction "A_SIDE") (pintype "bidirectional"))
    )
    (net (code "112") (name "Net-(U$55-A)") (class "Default")
      (node (ref "D55") (pin "A") (pinfunction "A_A") (pintype "passive"))
      (node (ref "U$55") (pin "SIDE") (pinfunction "A_SIDE") (pintype "bidirectional"))
    )
    (net (code "113") (name "Net-(U$56-A)") (class "Default")
      (node (ref "D56") (pin "A") (pinfunction "A_A") (pintype "passive"))
      (node (ref "U$56") (pin "SIDE") (pinfunction "A_SIDE") (pintype "bidirectional"))
    )
    (net (code "114") (name "Net-(U$57-A)") (class "Default")
      (node (ref "D57") (pin "A") (pinfunction "A_A") (pintype "passive"))
      (node (ref "U$57") (pin "SIDE") (pinfunction "A_SIDE") (pintype "bidirectional"))
    )
    (net (code "115") (name "Net-(U$58-A)") (class "Default")
      (node (ref "D58") (pin "A") (pinfunction "A_A") (pintype "passive"))
      (node (ref "U$58") (pin "SIDE") (pinfunction "A_SIDE") (pintype "bidirectional"))
    )
    (net (code "116") (name "Net-(U$59-A)") (class "Default")
      (node (ref "D59") (pin "A") (pinfunction "A_A") (pintype "passive"))
      (node (ref "U$59") (pin "SIDE") (pinfunction "A_SIDE") (pintype "bidirectional"))
    )
    (net (code "117") (name "Net-(U$60-A)") (class "Default")
      (node (ref "D60") (pin "A") (pinfunction "A_A") (pintype "passive"))
      (node (ref "U$60") (pin "SIDE") (pinfunction "A_SIDE") (pintype "bidirectional"))
    )
    (net (code "118") (name "Net-(U$61-A)") (class "Default")
      (node (ref "D61") (pin "A") (pinfunction "A_A") (pintype "passive"))
      (node (ref "U$61") (pin "SIDE") (pinfunction "A_SIDE") (pintype "bidirectional"))
    )
    (net (code "119") (name "Net-(U$62-A)") (class "Default")
      (node (ref "D62") (pin "A") (pinfunction "A_A") (pintype "passive"))
      (node (ref "U$62") (pin "SIDE") (pinfunction "A_SIDE") (pintype "bidirectional"))
    )
    (net (code "120") (name "Net-(U$63-A)") (class "Default")
      (node (ref "D63") (pin "A") (pinfunction "A_A") (pintype "passive"))
      (node (ref "U$63") (pin "SIDE") (pinfunction "A_SIDE") (pintype "bidirectional"))
    )
    (net (code "121") (name "Net-(U$64-A)") (class "Default")
      (node (ref "D64") (pin "A") (pinfunction "A_A") (pintype "passive"))
      (node (ref "U$64") (pin "SIDE") (pinfunction "A_SIDE") (pintype "bidirectional"))
    )
    (net (code "122") (name "Net-(U$65-A)") (class "Default")
      (node (ref "D65") (pin "A") (pinfunction "A_A") (pintype "passive"))
      (node (ref "U$65") (pin "SIDE") (pinfunction "A_SIDE") (pintype "bidirectional"))
    )
    (net (code "123") (name "Net-(U$66-A)") (class "Default")
      (node (ref "D66") (pin "A") (pinfunction "A_A") (pintype "passive"))
      (node (ref "U$66") (pin "SIDE") (pinfunction "A_SIDE") (pintype "bidirectional"))
    )
    (net (code "124") (name "Net-(U$67-A)") (class "Default")
      (node (ref "D67") (pin "A") (pinfunction "A_A") (pintype "passive"))
      (node (ref "U$67") (pin "SIDE") (pinfunction "A_SIDE") (pintype "bidirectional"))
    )
    (net (code "125") (name "Net-(U$68-A)") (class "Default")
      (node (ref "D68") (pin "A") (pinfunction "A_A") (pintype "passive"))
      (node (ref "U$68") (pin "SIDE") (pinfunction "A_SIDE") (pintype "bidirectional"))
    )
    (net (code "126") (name "Net-(U$69-A)") (class "Default")
      (node (ref "D69") (pin "A") (pinfunction "A_A") (pintype "passive"))
      (node (ref "U$69") (pin "SIDE") (pinfunction "A_SIDE") (pintype "bidirectional"))
    )
    (net (code "127") (name "Net-(U$70-A)") (class "Default")
      (node (ref "D70") (pin "A") (pinfunction "A_A") (pintype "passive"))
      (node (ref "U$70") (pin "SIDE") (pinfunction "A_SIDE") (pintype "bidirectional"))
    )
    (net (code "128") (name "Net-(U$71-A)") (class "Default")
      (node (ref "D71") (pin "A") (pinfunction "A_A") (pintype "passive"))
      (node (ref "U$71") (pin "SIDE") (pinfunction "A_SIDE") (pintype "bidirectional"))
    )
    (net (code "129") (name "Net-(U$72-A)") (class "Default")
      (node (ref "D72") (pin "A") (pinfunction "A_A") (pintype "passive"))
      (node (ref "U$72") (pin "SIDE") (pinfunction "A_SIDE") (pintype "bidirectional"))
    )
    (net (code "130") (name "Net-(U$73-A)") (class "Default")
      (node (ref "D73") (pin "A") (pinfunction "A_A") (pintype "passive"))
      (node (ref "U$73") (pin "SIDE") (pinfunction "A_SIDE") (pintype "bidirectional"))
    )
    (net (code "131") (name "Net-(U$74-A)") (class "Default")
      (node (ref "D74") (pin "A") (pinfunction "A_A") (pintype "passive"))
      (node (ref "U$74") (pin "SIDE") (pinfunction "A_SIDE") (pintype "bidirectional"))
    )
    (net (code "132") (name "Net-(U$75-A)") (class "Default")
      (node (ref "D75") (pin "A") (pinfunction "A_A") (pintype "passive"))
      (node (ref "U$75") (pin "SIDE") (pinfunction "A_SIDE") (pintype "bidirectional"))
    )
    (net (code "133") (name "unconnected-(IC1-PC0_(SCL)-Pad22)") (class "Default")
      (node (ref "IC1") (pin "22") (pinfunction "PC0_(SCL)_22") (pintype "bidirectional"))
    )
    (net (code "134") (name "unconnected-(IC1-PC1_(SDA)-Pad23)") (class "Default")
      (node (ref "IC1") (pin "23") (pinfunction "PC1_(SDA)_23") (pintype "bidirectional"))
    )
    (net (code "135") (name "unconnected-(IC1-PC2_(TCK)-Pad24)") (class "Default")
      (node (ref "IC1") (pin "24") (pinfunction "PC2_(TCK)_24") (pintype "bidirectional"))
    )
    (net (code "136") (name "unconnected-(IC1-PC3_(TMS)-Pad25)") (class "Default")
      (node (ref "IC1") (pin "25") (pinfunction "PC3_(TMS)_25") (pintype "bidirectional"))
    )
    (net (code "137") (name "unconnected-(IC1-PC4_(TDO)-Pad26)") (class "Default")
      (node (ref "IC1") (pin "26") (pinfunction "PC4_(TDO)_26") (pintype "bidirectional"))
    )
    (net (code "138") (name "unconnected-(IC1-PD7_(OC2)-Pad21)") (class "Default")
      (node (ref "IC1") (pin "21") (pinfunction "PD7_(OC2)_21") (pintype "bidirectional"))
    )
    (net (code "139") (name "unconnected-(J1-SBU1-PadA8)") (class "Default")
      (node (ref "J1") (pin "A8") (pinfunction "SBU1_A8") (pintype "bidirectional"))
    )
    (net (code "140") (name "unconnected-(J1-SBU2-PadB8)") (class "Default")
      (node (ref "J1") (pin "B8") (pinfunction "SBU2_B8") (pintype "bidirectional"))
    )
    (net (code "141") (name "unconnected-(LED14-DO-Pad2)") (class "Default")
      (node (ref "LED14") (pin "2") (pinfunction "DO_2") (pintype "bidirectional"))
    )
    (net (code "142") (name "unconnected-(S1-Pad2)") (class "Default")
      (node (ref "S1") (pin "2") (pinfunction "2_2") (pintype "passive"))
    )
    (net (code "143") (name "unconnected-(S1-Pad4)") (class "Default")
      (node (ref "S1") (pin "4") (pinfunction "4_4") (pintype "passive"))
    )
    (net (code "144") (name "unconnected-(S2-Pad2)") (class "Default")
      (node (ref "S2") (pin "2") (pinfunction "2_2") (pintype "passive"))
    )
    (net (code "145") (name "unconnected-(S2-Pad4)") (class "Default")
      (node (ref "S2") (pin "4") (pinfunction "4_4") (pintype "passive"))
    )
  )
)
